# pc_healthypi_5_7.net
KiCad netlist of a schematic drawn in EAGLE
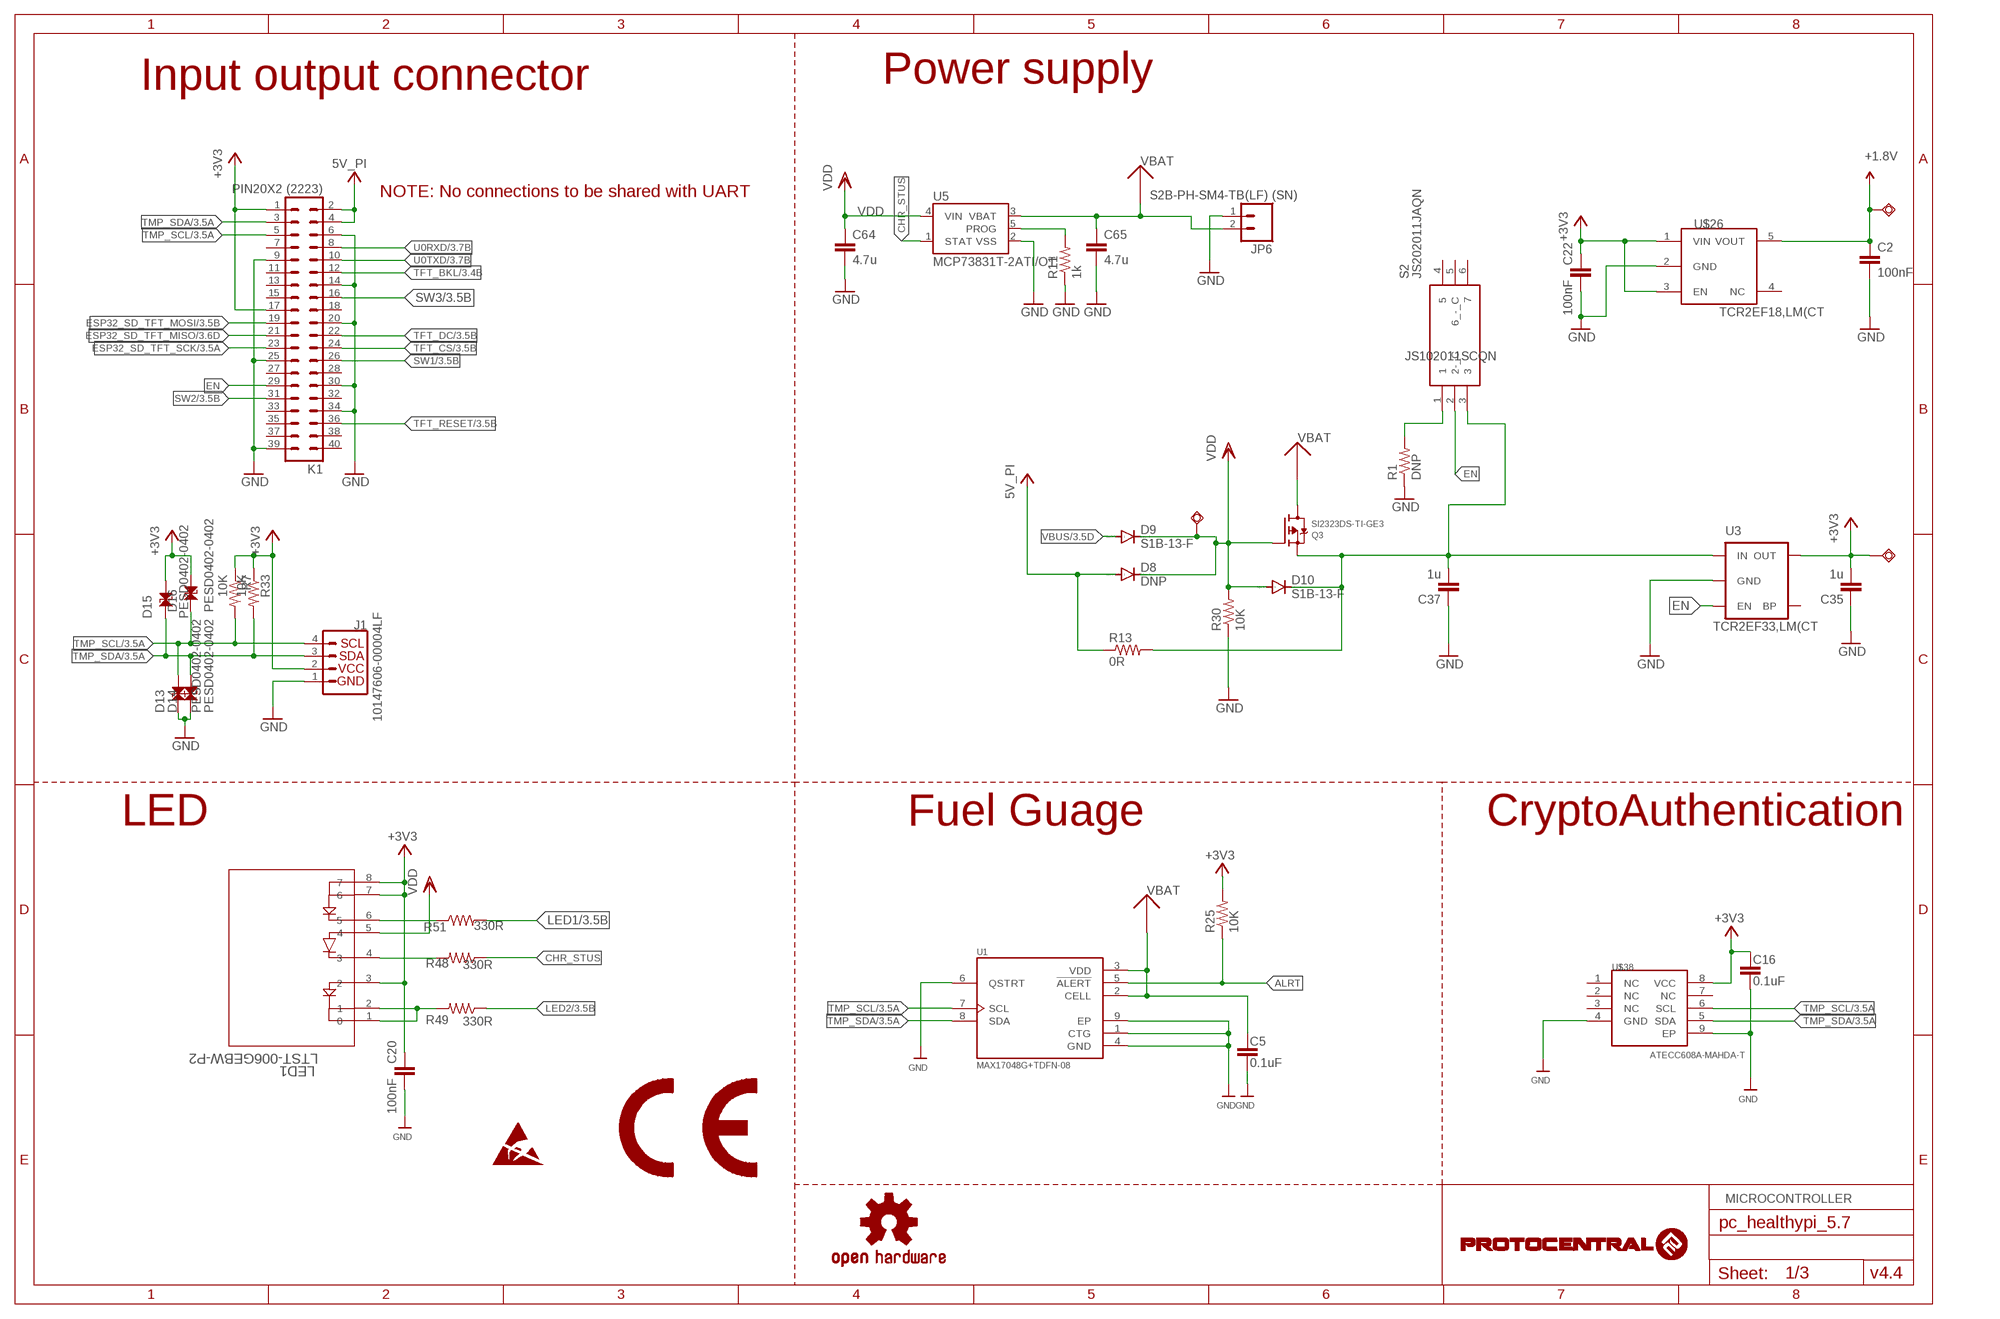
[diagram p0: schematic, sheet 1]
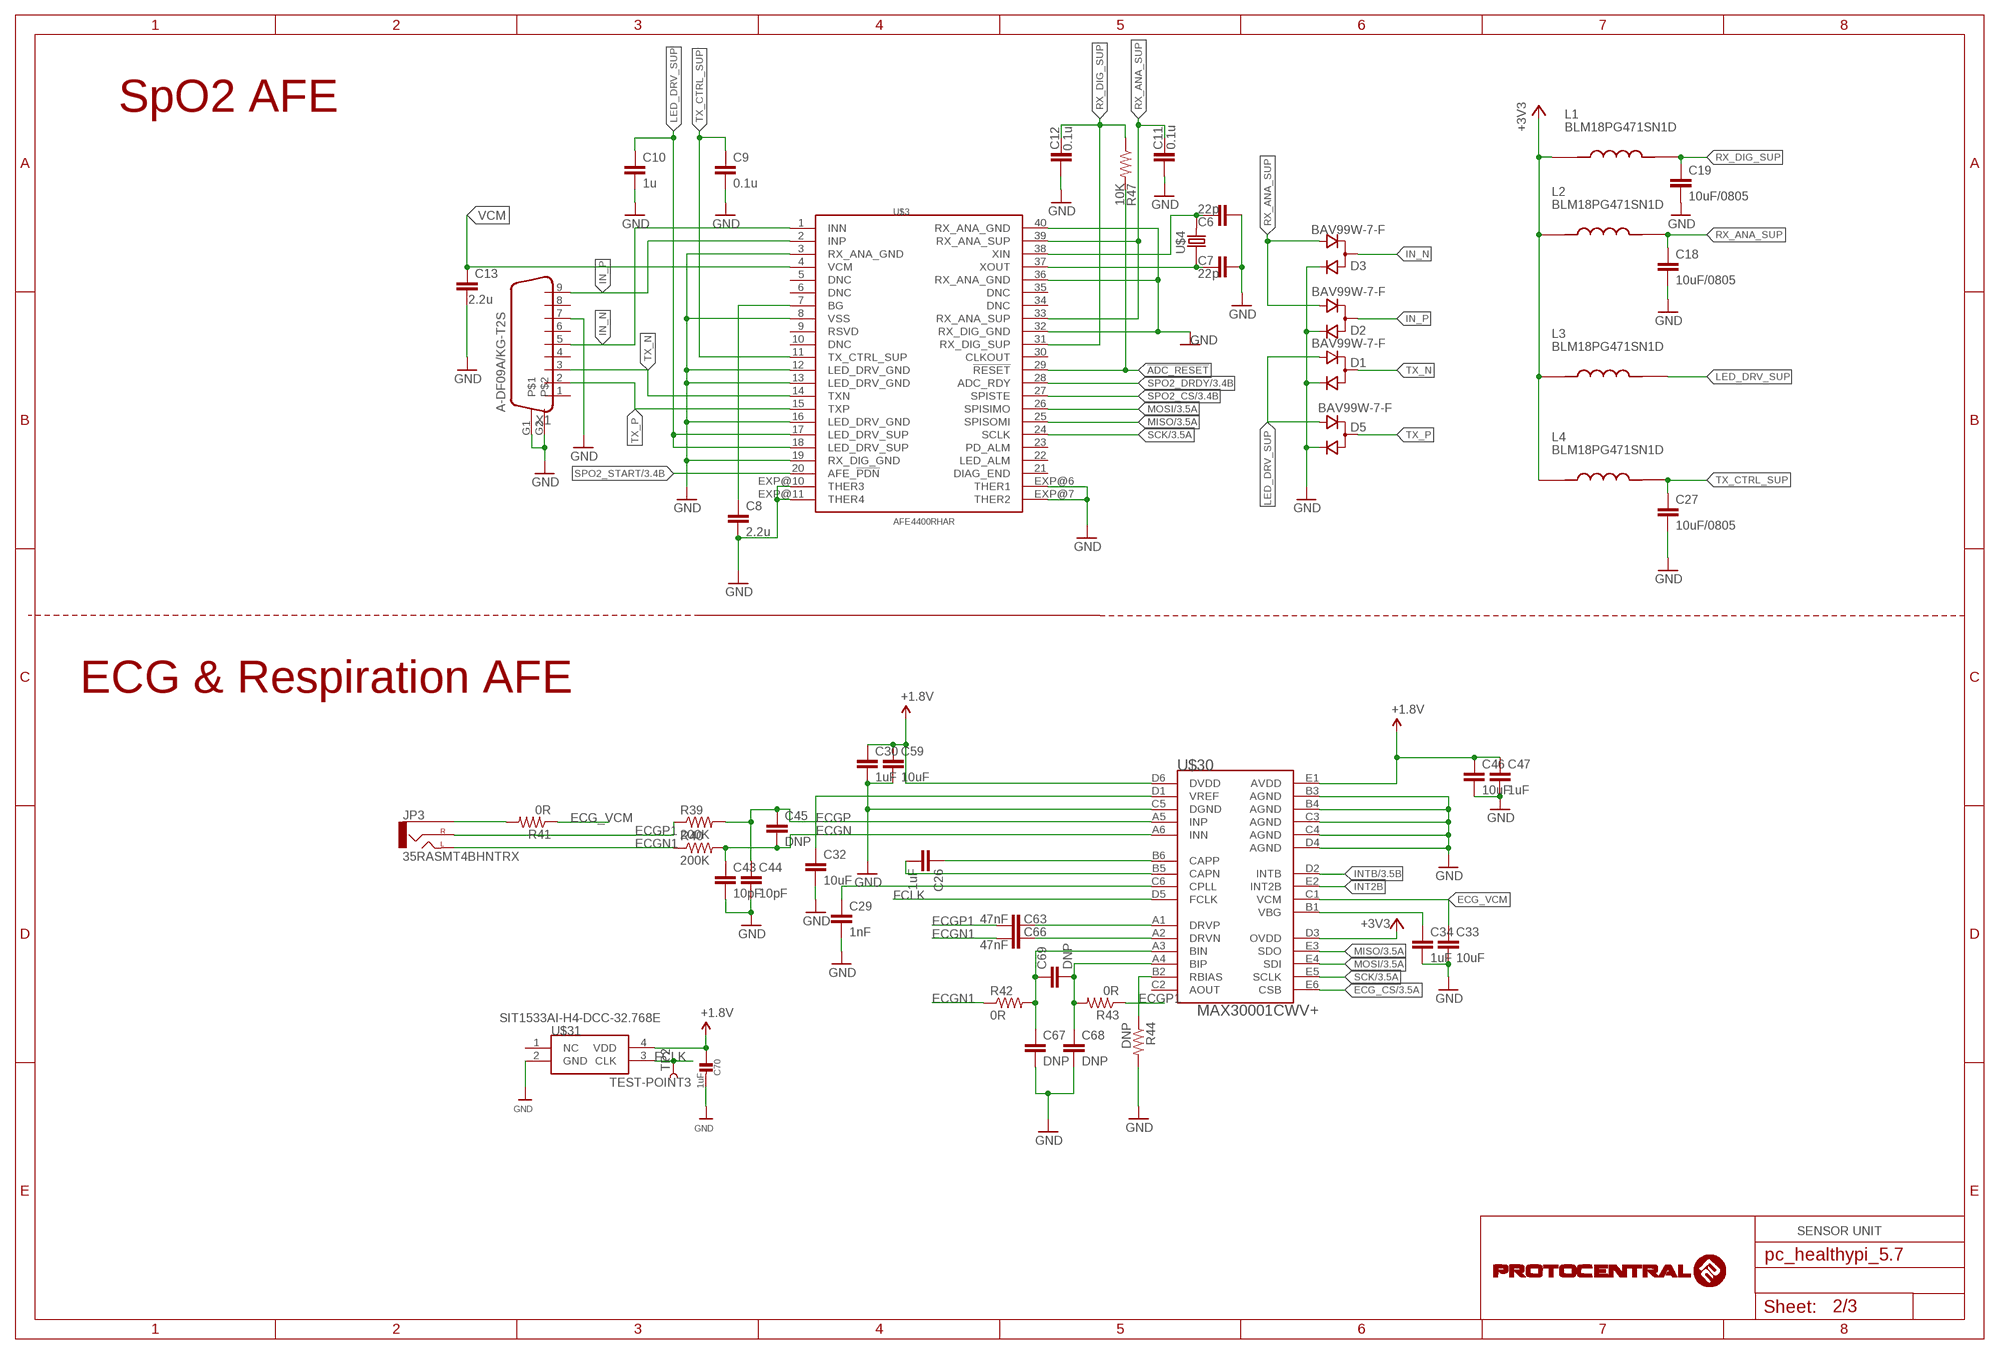
[diagram p1: schematic, sheet 2]
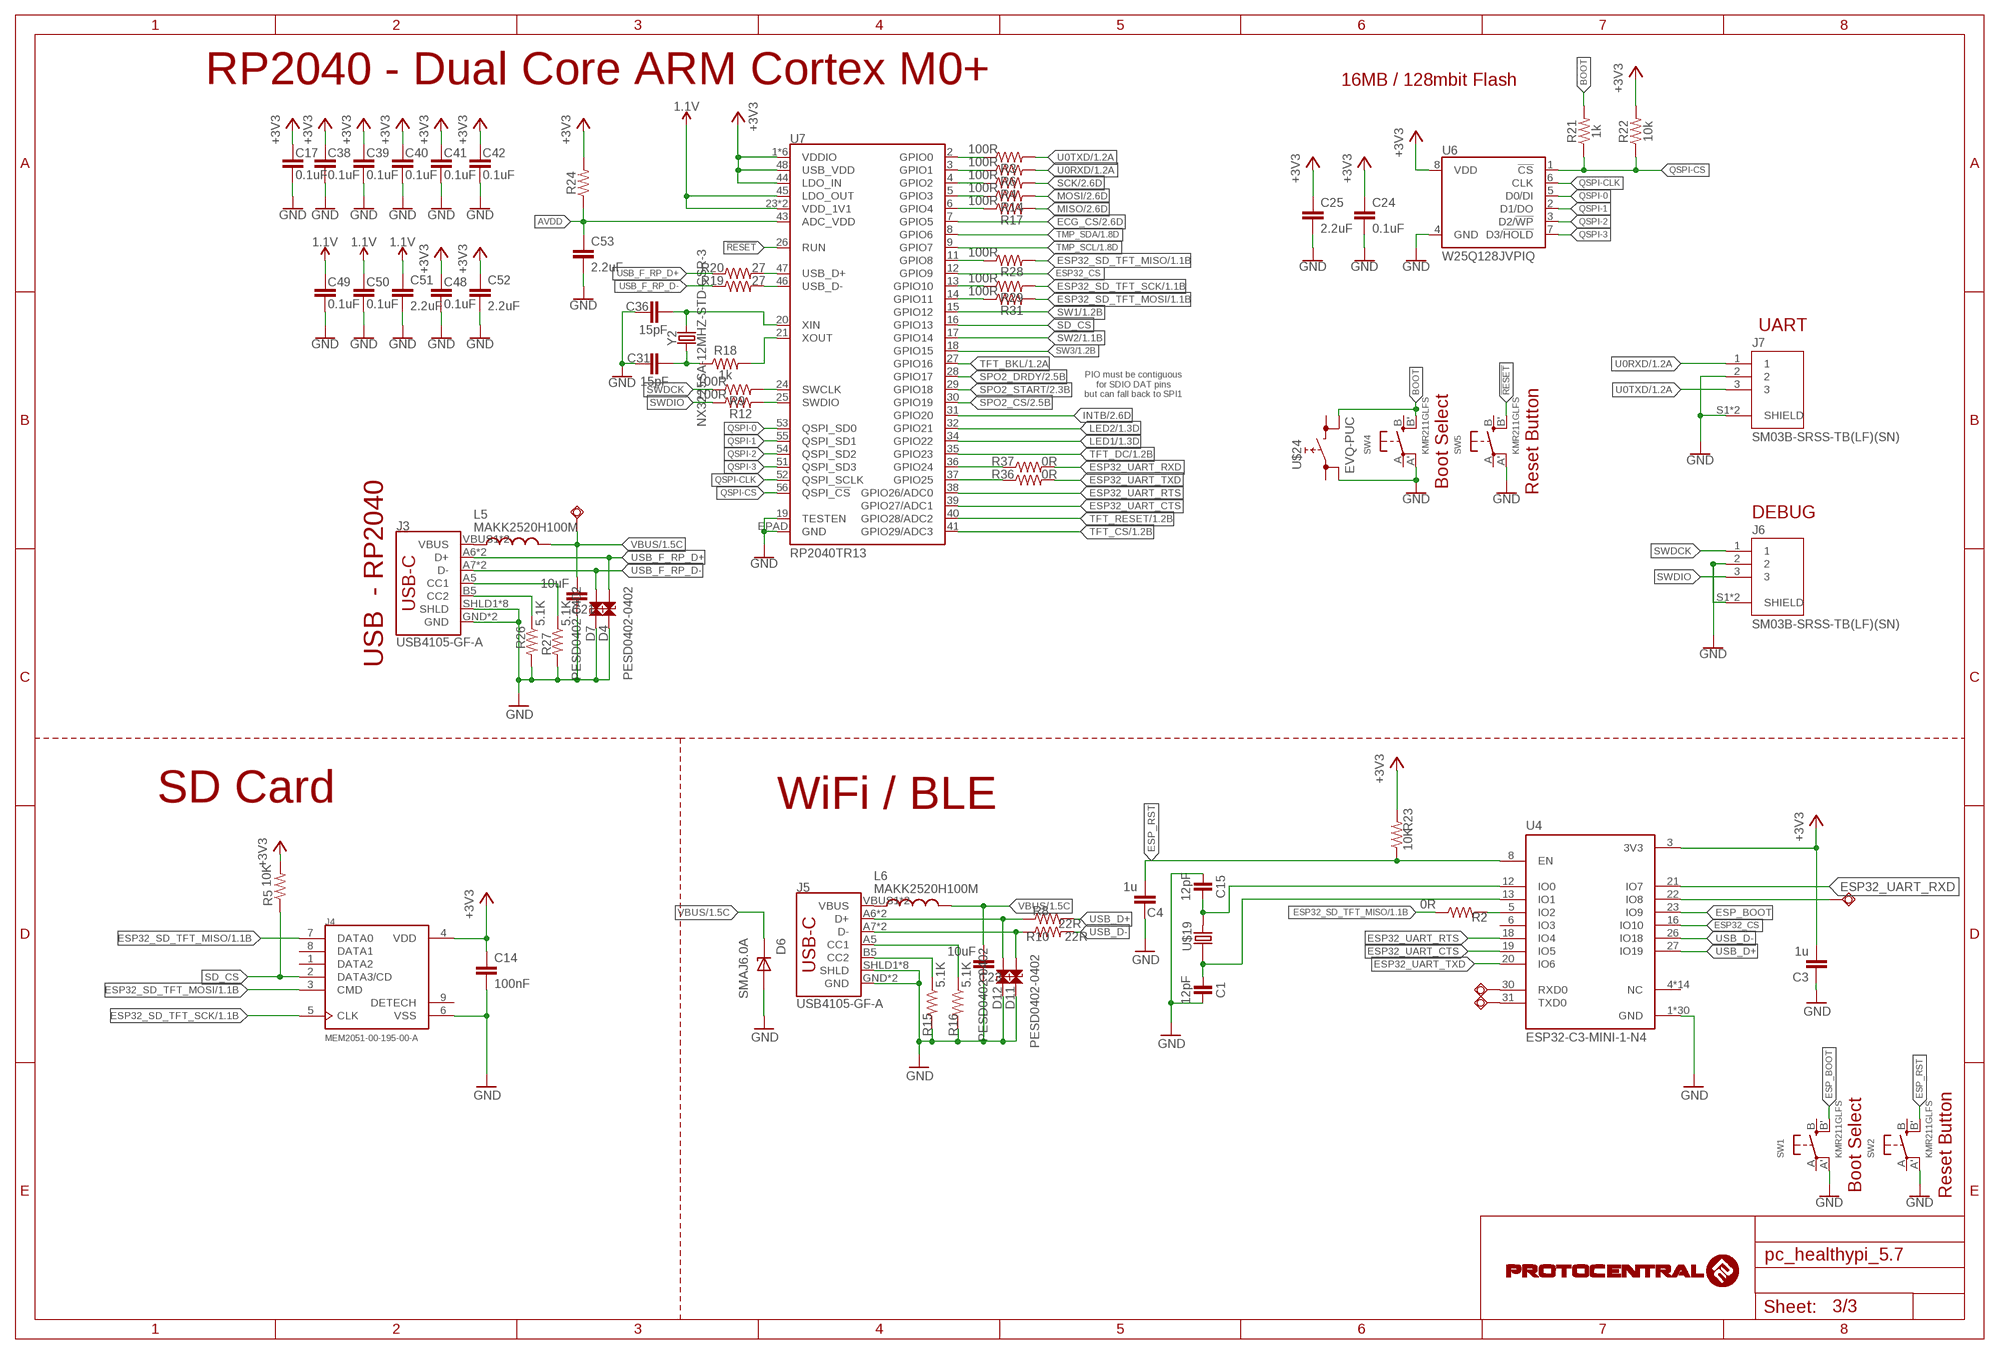
[diagram p2: schematic, sheet 3]

(export (version "E")
  (design (tool "Eeschema 10.0.6"))
  (components
    (comp (ref "C6")
      (value "22p")
      (footprint "eagle-import:C0402")
      (libsource (lib "eagle-import") (part "rcl_334_C-EUC0402"))
    )
    (comp (ref "C7")
      (value "22p")
      (footprint "eagle-import:C0402")
      (libsource (lib "eagle-import") (part "rcl_334_C-EUC0402"))
    )
    (comp (ref "C8")
      (value "2.2u")
      (footprint "eagle-import:C0402")
      (libsource (lib "eagle-import") (part "rcl_334_C-EUC0402"))
    )
    (comp (ref "C9")
      (value "0.1u")
      (footprint "eagle-import:C0402")
      (libsource (lib "eagle-import") (part "rcl_334_C-EUC0402"))
    )
    (comp (ref "C10")
      (value "1u")
      (footprint "eagle-import:C0805")
      (libsource (lib "eagle-import") (part "rcl_334_C-EUC0805"))
    )
    (comp (ref "C11")
      (value "0.1u")
      (footprint "eagle-import:C0402")
      (libsource (lib "eagle-import") (part "rcl_334_C-EUC0402"))
    )
    (comp (ref "C12")
      (value "0.1u")
      (footprint "eagle-import:C0402")
      (libsource (lib "eagle-import") (part "rcl_334_C-EUC0402"))
    )
    (comp (ref "C13")
      (value "2.2u")
      (footprint "eagle-import:C0402")
      (libsource (lib "eagle-import") (part "rcl_334_C-EUC0402"))
    )
    (comp (ref "C18")
      (value "10uF/0805")
      (footprint "eagle-import:C0805")
      (libsource (lib "eagle-import") (part "rcl_334_C-EUC0805"))
    )
    (comp (ref "C19")
      (value "10uF/0805")
      (footprint "eagle-import:C0805")
      (libsource (lib "eagle-import") (part "rcl_334_C-EUC0805"))
    )
    (comp (ref "C26")
      (value "1uF")
      (footprint "eagle-import:C0805")
      (libsource (lib "eagle-import") (part "rcl_334_C-EUC0805"))
    )
    (comp (ref "C27")
      (value "10uF/0805")
      (footprint "eagle-import:C0805")
      (libsource (lib "eagle-import") (part "rcl_334_C-EUC0805"))
    )
    (comp (ref "C29")
      (value "1nF")
      (footprint "eagle-import:C0402")
      (libsource (lib "eagle-import") (part "rcl_334_C-EUC0402"))
    )
    (comp (ref "C30")
      (value "1uF")
      (footprint "eagle-import:C0402")
      (libsource (lib "eagle-import") (part "rcl_334_C-EUC0402"))
    )
    (comp (ref "C32")
      (value "10uF")
      (footprint "eagle-import:C0805")
      (libsource (lib "eagle-import") (part "rcl_334_C-EUC0805"))
    )
    (comp (ref "C33")
      (value "10uF")
      (footprint "eagle-import:C0805")
      (libsource (lib "eagle-import") (part "rcl_334_C-EUC0805"))
    )
    (comp (ref "C34")
      (value "1uF")
      (footprint "eagle-import:C0402")
      (libsource (lib "eagle-import") (part "rcl_334_C-EUC0402"))
    )
    (comp (ref "C43")
      (value "10pF")
      (footprint "eagle-import:C0402")
      (libsource (lib "eagle-import") (part "rcl_334_C-EUC0402"))
    )
    (comp (ref "C44")
      (value "10pF")
      (footprint "eagle-import:C0402")
      (libsource (lib "eagle-import") (part "rcl_334_C-EUC0402"))
    )
    (comp (ref "C45")
      (value "DNP")
      (footprint "eagle-import:C0402")
      (libsource (lib "eagle-import") (part "rcl_334_C-EUC0402"))
    )
    (comp (ref "C46")
      (value "10uF")
      (footprint "eagle-import:C0805")
      (libsource (lib "eagle-import") (part "rcl_334_C-EUC0805"))
    )
    (comp (ref "C47")
      (value "1uF")
      (footprint "eagle-import:C0402")
      (libsource (lib "eagle-import") (part "rcl_334_C-EUC0402"))
    )
    (comp (ref "C59")
      (value "10uF")
      (footprint "eagle-import:C0805")
      (libsource (lib "eagle-import") (part "rcl_334_C-EUC0805"))
    )
    (comp (ref "C63")
      (value "47nF")
      (footprint "eagle-import:C0402")
      (libsource (lib "eagle-import") (part "rcl_334_C-EUC0402"))
    )
    (comp (ref "C66")
      (value "47nF")
      (footprint "eagle-import:C0402")
      (libsource (lib "eagle-import") (part "rcl_334_C-EUC0402"))
    )
    (comp (ref "C67")
      (value "DNP")
      (footprint "eagle-import:C0402")
      (libsource (lib "eagle-import") (part "rcl_334_C-EUC0402"))
    )
    (comp (ref "C68")
      (value "DNP")
      (footprint "eagle-import:C0402")
      (libsource (lib "eagle-import") (part "rcl_334_C-EUC0402"))
    )
    (comp (ref "C69")
      (value "DNP")
      (footprint "eagle-import:C0402")
      (libsource (lib "eagle-import") (part "rcl_334_C-EUC0402"))
    )
    (comp (ref "C70")
      (value "1uF")
      (footprint "eagle-import:0402")
      (libsource (lib "eagle-import") (part "CAP_CERAMIC0402"))
    )
    (comp (ref "D1")
      (value "BAV99W-7-F")
      (footprint "eagle-import:SOT323")
      (libsource (lib "eagle-import") (part "D_ACACSOT323"))
    )
    (comp (ref "D2")
      (value "BAV99W-7-F")
      (footprint "eagle-import:SOT323")
      (libsource (lib "eagle-import") (part "D_ACACSOT323"))
    )
    (comp (ref "D3")
      (value "BAV99W-7-F")
      (footprint "eagle-import:SOT323")
      (libsource (lib "eagle-import") (part "D_ACACSOT323"))
    )
    (comp (ref "D5")
      (value "BAV99W-7-F")
      (footprint "eagle-import:SOT323")
      (libsource (lib "eagle-import") (part "D_ACACSOT323"))
    )
    (comp (ref "JP3")
      (value "35RASMT4BHNTRX")
      (footprint "eagle-import:AUDIO-JACK-3.5MM-SMD")
      (libsource (lib "eagle-import") (part "AUDIO-JACKSMD2"))
    )
    (comp (ref "L1")
      (value "BLM18PG471SN1D")
      (footprint "eagle-import:INDC2012X105N")
      (fields (field (name "MF") "TDK") (field (name "MP") "MLZ2012N2R2LT000"))
      (libsource (lib "eagle-import") (part "MLZ2012N2R2LT000"))
    )
    (comp (ref "L2")
      (value "BLM18PG471SN1D")
      (footprint "eagle-import:INDC2012X105N")
      (fields (field (name "MF") "TDK") (field (name "MP") "MLZ2012N2R2LT000"))
      (libsource (lib "eagle-import") (part "MLZ2012N2R2LT000"))
    )
    (comp (ref "L3")
      (value "BLM18PG471SN1D")
      (footprint "eagle-import:INDC2012X105N")
      (fields (field (name "MF") "TDK") (field (name "MP") "MLZ2012N2R2LT000"))
      (libsource (lib "eagle-import") (part "MLZ2012N2R2LT000"))
    )
    (comp (ref "L4")
      (value "BLM18PG471SN1D")
      (footprint "eagle-import:INDC2012X105N")
      (fields (field (name "MF") "TDK") (field (name "MP") "MLZ2012N2R2LT000"))
      (libsource (lib "eagle-import") (part "MLZ2012N2R2LT000"))
    )
    (comp (ref "R39")
      (value "200K")
      (footprint "eagle-import:0805")
      (libsource (lib "eagle-import") (part "RESISTOR0805-RES"))
    )
    (comp (ref "R40")
      (value "200K")
      (footprint "eagle-import:0805")
      (libsource (lib "eagle-import") (part "RESISTOR0805-RES"))
    )
    (comp (ref "R41")
      (value "0R")
      (footprint "eagle-import:0805")
      (libsource (lib "eagle-import") (part "RESISTOR0805-RES"))
    )
    (comp (ref "R42")
      (value "0R")
      (footprint "eagle-import:0402-RES")
      (libsource (lib "eagle-import") (part "RESISTOR0402-RES"))
    )
    (comp (ref "R43")
      (value "0R")
      (footprint "eagle-import:0402-RES")
      (libsource (lib "eagle-import") (part "RESISTOR0402-RES"))
    )
    (comp (ref "R44")
      (value "DNP")
      (footprint "eagle-import:0402-RES")
      (libsource (lib "eagle-import") (part "RESISTOR0402-RES"))
    )
    (comp (ref "R47")
      (value "10K")
      (footprint "eagle-import:R0402")
      (libsource (lib "eagle-import") (part "rcl_334_R-US_R0402"))
    )
    (comp (ref "TP2")
      (value "TEST-POINT3")
      (footprint "eagle-import:PAD.03X.03")
      (libsource (lib "eagle-import") (part "TEST-POINT3"))
    )
    (comp (ref "U$3")
      (value "AFE4400RHAR")
      (footprint "eagle-import:QFN-40")
      (libsource (lib "eagle-import") (part "AFE4400"))
    )
    (comp (ref "U$4")
      (value "ABM3")
      (footprint "eagle-import:ABM3")
      (libsource (lib "eagle-import") (part "ABM3"))
    )
    (comp (ref "U$30")
      (value "MAX30001CWV+")
      (footprint "eagle-import:30WLP")
      (libsource (lib "eagle-import") (part "MAX30001CWV+"))
    )
    (comp (ref "U$31")
      (value "SIT1533AI-H4-DCC-32.768E")
      (footprint "eagle-import:SIT1533")
      (libsource (lib "eagle-import") (part "SIT1533"))
    )
    (comp (ref "X1")
      (value "A-DF09A/KG-T2S")
      (footprint "eagle-import:DB9")
      (libsource (lib "eagle-import") (part "DB9"))
    )
    (comp (ref "C2")
      (value "100nF")
      (footprint "eagle-import:C0402")
      (libsource (lib "eagle-import") (part "rcl_334_C-EUC0402"))
    )
    (comp (ref "C5")
      (value "0.1uF")
      (footprint "eagle-import:0402-TIGHT")
      (libsource (lib "eagle-import") (part "0.1UF-0402T-6.3V-10%-X7R"))
    )
    (comp (ref "C16")
      (value "0.1uF")
      (footprint "eagle-import:0402-TIGHT")
      (libsource (lib "eagle-import") (part "0.1UF-0402T-6.3V-10%-X7R"))
    )
    (comp (ref "C20")
      (value "100nF")
      (footprint "eagle-import:C0402")
      (libsource (lib "eagle-import") (part "rcl_334_C-EUC0402"))
    )
    (comp (ref "C22")
      (value "100nF")
      (footprint "eagle-import:C0402")
      (libsource (lib "eagle-import") (part "rcl_334_C-EUC0402"))
    )
    (comp (ref "C35")
      (value "1u")
      (footprint "eagle-import:C0402")
      (libsource (lib "eagle-import") (part "rcl_334_C-EUC0402"))
    )
    (comp (ref "C37")
      (value "1u")
      (footprint "eagle-import:C0402")
      (libsource (lib "eagle-import") (part "rcl_334_C-EUC0402"))
    )
    (comp (ref "C64")
      (value "4.7u")
      (footprint "eagle-import:C0805")
      (libsource (lib "eagle-import") (part "rcl_334_C-EUC0805"))
    )
    (comp (ref "C65")
      (value "4.7u")
      (footprint "eagle-import:C0805")
      (libsource (lib "eagle-import") (part "rcl_334_C-EUC0805"))
    )
    (comp (ref "D8")
      (value "DNP")
      (footprint "eagle-import:SOD-123_MINI-SMA")
      (libsource (lib "eagle-import") (part "CGRM400-G1"))
    )
    (comp (ref "D9")
      (value "S1B-13-F")
      (footprint "eagle-import:SOD-123_MINI-SMA")
      (libsource (lib "eagle-import") (part "CGRM400-G1"))
    )
    (comp (ref "D10")
      (value "S1B-13-F")
      (footprint "eagle-import:SOD-123_MINI-SMA")
      (libsource (lib "eagle-import") (part "CGRM400-G1"))
    )
    (comp (ref "D13")
      (value "PESD0402-0402")
      (footprint "eagle-import:0402")
      (fields
        (field (name "DIGIKEY_PART") "PESD0402-140CT-ND")
        (field (name "MOUSE_PART") "650-PESD0402-140")
      )
      (libsource (lib "eagle-import") (part "PESD0402-0402"))
    )
    (comp (ref "D14")
      (value "PESD0402-0402")
      (footprint "eagle-import:0402")
      (fields
        (field (name "DIGIKEY_PART") "PESD0402-140CT-ND")
        (field (name "MOUSE_PART") "650-PESD0402-140")
      )
      (libsource (lib "eagle-import") (part "PESD0402-0402"))
    )
    (comp (ref "D15")
      (value "PESD0402-0402")
      (footprint "eagle-import:0402")
      (fields
        (field (name "DIGIKEY_PART") "PESD0402-140CT-ND")
        (field (name "MOUSE_PART") "650-PESD0402-140")
      )
      (libsource (lib "eagle-import") (part "PESD0402-0402"))
    )
    (comp (ref "D16")
      (value "PESD0402-0402")
      (footprint "eagle-import:0402")
      (fields
        (field (name "DIGIKEY_PART") "PESD0402-140CT-ND")
        (field (name "MOUSE_PART") "650-PESD0402-140")
      )
      (libsource (lib "eagle-import") (part "PESD0402-0402"))
    )
    (comp (ref "J1")
      (value "10147606-00004LF")
      (footprint "eagle-import:JST04_1MM_RA")
      (libsource (lib "eagle-import") (part "QWIIC_CONNECTORJS-1MM"))
    )
    (comp (ref "JP6")
      (value "S2B-PH-SM4-TB(LF) (SN)")
      (footprint "eagle-import:JST-2-SMD")
      (libsource (lib "eagle-import") (part "M02-JST-2MM-SMT"))
    )
    (comp (ref "K1")
      (value "PIN20X2 (2223)")
      (footprint "eagle-import:PIN_20X2")
      (libsource (lib "eagle-import") (part "PIN20X2"))
    )
    (comp (ref "LED1")
      (value "LTST-006GEBW-P2")
      (footprint "eagle-import:LTST-008BGEW_LTO")
      (fields (field (name "COPYRIGHT") "Copyright (C) 2023 Ultra Librarian. All rights reserved."))
      (libsource (lib "eagle-import") (part "LTST-006GEBW-P2"))
    )
    (comp (ref "Q3")
      (value "SI2323DS-TI-GE3")
      (footprint "eagle-import:SOT23-R")
      (libsource (lib "eagle-import") (part "MOSFET-P"))
    )
    (comp (ref "R1")
      (value "DNP")
      (footprint "eagle-import:R0402")
      (libsource (lib "eagle-import") (part "rcl_334_R-US_R0402"))
    )
    (comp (ref "R7")
      (value "10K")
      (footprint "eagle-import:R0402")
      (libsource (lib "eagle-import") (part "rcl_334_R-US_R0402"))
    )
    (comp (ref "R11")
      (value "1k")
      (footprint "eagle-import:R0402")
      (libsource (lib "eagle-import") (part "rcl_334_R-US_R0402"))
    )
    (comp (ref "R13")
      (value "0R")
      (footprint "eagle-import:0805")
      (libsource (lib "eagle-import") (part "RESISTOR0805-RES"))
    )
    (comp (ref "R25")
      (value "10K")
      (footprint "eagle-import:0402-RES")
      (libsource (lib "eagle-import") (part "RESISTOR0402-RES"))
    )
    (comp (ref "R30")
      (value "10K")
      (footprint "eagle-import:R0402")
      (libsource (lib "eagle-import") (part "rcl_334_R-US_R0402"))
    )
    (comp (ref "R33")
      (value "10K")
      (footprint "eagle-import:R0402")
      (libsource (lib "eagle-import") (part "rcl_334_R-US_R0402"))
    )
    (comp (ref "R48")
      (value "330R")
      (footprint "eagle-import:0402-RES")
      (libsource (lib "eagle-import") (part "RESISTOR0402-RES"))
    )
    (comp (ref "R49")
      (value "330R")
      (footprint "eagle-import:0402-RES")
      (libsource (lib "eagle-import") (part "RESISTOR0402-RES"))
    )
    (comp (ref "R51")
      (value "330R")
      (footprint "eagle-import:0402-RES")
      (libsource (lib "eagle-import") (part "RESISTOR0402-RES"))
    )
    (comp (ref "S2")
      (value "JS202011JAQN")
      (footprint "eagle-import:JS202011JAQN")
      (fields (field (name "MF") "C&K"))
      (libsource (lib "eagle-import") (part "JS202011JAQN"))
    )
    (comp (ref "SWIO1")
      (value "TPSQTP11R")
      (footprint "eagle-import:TP11R")
      (libsource (lib "eagle-import") (part "TPSQTP11R"))
    )
    (comp (ref "SWIO5")
      (value "TPSQTP11R")
      (footprint "eagle-import:TP11R")
      (libsource (lib "eagle-import") (part "TPSQTP11R"))
    )
    (comp (ref "SWIO7")
      (value "TPSQTP11R")
      (footprint "eagle-import:TP11R")
      (libsource (lib "eagle-import") (part "TPSQTP11R"))
    )
    (comp (ref "U$5")
      (value "OSHW-LOGOM")
      (footprint "eagle-import:OSHW-LOGO-M")
      (libsource (lib "eagle-import") (part "OSHW-LOGOM"))
    )
    (comp (ref "U$26")
      (value "TCR2EF18,LM(CT")
      (footprint "eagle-import:SOT95P285X140-5N")
      (libsource (lib "eagle-import") (part "AP7354D-18W5-7"))
    )
    (comp (ref "U$38")
      (value "ATECC608A-MAHDA-T")
      (footprint "eagle-import:PSON50P200X300X60-9N")
      (libsource (lib "eagle-import") (part "ATECC608B-TFLXTLS"))
    )
    (comp (ref "U1")
      (value "MAX17048G+TDFN-08")
      (footprint "eagle-import:SON50P200X200X80-9N")
      (fields (field (name "MF") "Analog Devices") (field (name "MP") "MAX17048G+"))
      (libsource (lib "eagle-import") (part "MAX17048G+TDFN-08"))
    )
    (comp (ref "U3")
      (value "TCR2EF33,LM(CT")
      (footprint "eagle-import:SOT23-5")
      (libsource (lib "eagle-import") (part "V_REG_LDOSMD"))
    )
    (comp (ref "U5")
      (value "MCP73831T-2ATI/OT")
      (footprint "eagle-import:SOT23-5")
      (libsource (lib "eagle-import") (part "MCP73831"))
    )
    (comp (ref "C1")
      (value "12pF")
      (footprint "eagle-import:C0402")
      (libsource (lib "eagle-import") (part "CAPACITORS-0402"))
    )
    (comp (ref "C3")
      (value "1u")
      (footprint "eagle-import:C0402")
      (libsource (lib "eagle-import") (part "rcl_334_C-EUC0402"))
    )
    (comp (ref "C4")
      (value "1u")
      (footprint "eagle-import:C0402")
      (libsource (lib "eagle-import") (part "rcl_334_C-EUC0402"))
    )
    (comp (ref "C14")
      (value "100nF")
      (footprint "eagle-import:C0402")
      (libsource (lib "eagle-import") (part "C-EUC0402"))
    )
    (comp (ref "C15")
      (value "12pF")
      (footprint "eagle-import:C0402")
      (libsource (lib "eagle-import") (part "CAPACITORS-0402"))
    )
    (comp (ref "C17")
      (value "0.1uF")
      (footprint "eagle-import:0402-TIGHT")
      (libsource (lib "eagle-import") (part "0.1UF-0402T-6.3V-10%-X7R"))
    )
    (comp (ref "C21")
      (value "10uF")
      (footprint "eagle-import:C0805")
      (libsource (lib "eagle-import") (part "rcl_334_C-EUC0805"))
    )
    (comp (ref "C23")
      (value "10uF")
      (footprint "eagle-import:C0805")
      (libsource (lib "eagle-import") (part "rcl_334_C-EUC0805"))
    )
    (comp (ref "C24")
      (value "0.1uF")
      (footprint "eagle-import:0402-TIGHT")
      (libsource (lib "eagle-import") (part "0.1UF-0402T-6.3V-10%-X7R"))
    )
    (comp (ref "C25")
      (value "2.2uF")
      (footprint "eagle-import:0402-TIGHT")
      (libsource (lib "eagle-import") (part "2.2UF-0402_TIGHT-10V-10%-X5R"))
    )
    (comp (ref "C31")
      (value "15pF")
      (footprint "eagle-import:0402-TIGHT")
      (libsource (lib "eagle-import") (part "15PF-0402T-50V-5%"))
    )
    (comp (ref "C36")
      (value "15pF")
      (footprint "eagle-import:0402-TIGHT")
      (libsource (lib "eagle-import") (part "15PF-0402T-50V-5%"))
    )
    (comp (ref "C38")
      (value "0.1uF")
      (footprint "eagle-import:0402-TIGHT")
      (libsource (lib "eagle-import") (part "0.1UF-0402T-6.3V-10%-X7R"))
    )
    (comp (ref "C39")
      (value "0.1uF")
      (footprint "eagle-import:0402-TIGHT")
      (libsource (lib "eagle-import") (part "0.1UF-0402T-6.3V-10%-X7R"))
    )
    (comp (ref "C40")
      (value "0.1uF")
      (footprint "eagle-import:0402-TIGHT")
      (libsource (lib "eagle-import") (part "0.1UF-0402T-6.3V-10%-X7R"))
    )
    (comp (ref "C41")
      (value "0.1uF")
      (footprint "eagle-import:0402-TIGHT")
      (libsource (lib "eagle-import") (part "0.1UF-0402T-6.3V-10%-X7R"))
    )
    (comp (ref "C42")
      (value "0.1uF")
      (footprint "eagle-import:0402-TIGHT")
      (libsource (lib "eagle-import") (part "0.1UF-0402T-6.3V-10%-X7R"))
    )
    (comp (ref "C48")
      (value "0.1uF")
      (footprint "eagle-import:0402-TIGHT")
      (libsource (lib "eagle-import") (part "0.1UF-0402T-6.3V-10%-X7R"))
    )
    (comp (ref "C49")
      (value "0.1uF")
      (footprint "eagle-import:0402-TIGHT")
      (libsource (lib "eagle-import") (part "0.1UF-0402T-6.3V-10%-X7R"))
    )
    (comp (ref "C50")
      (value "0.1uF")
      (footprint "eagle-import:0402-TIGHT")
      (libsource (lib "eagle-import") (part "0.1UF-0402T-6.3V-10%-X7R"))
    )
    (comp (ref "C51")
      (value "2.2uF")
      (footprint "eagle-import:0402-TIGHT")
      (libsource (lib "eagle-import") (part "2.2UF-0402_TIGHT-10V-10%-X5R"))
    )
    (comp (ref "C52")
      (value "2.2uF")
      (footprint "eagle-import:0402-TIGHT")
      (libsource (lib "eagle-import") (part "2.2UF-0402_TIGHT-10V-10%-X5R"))
    )
    (comp (ref "C53")
      (value "2.2uF")
      (footprint "eagle-import:0402-TIGHT")
      (libsource (lib "eagle-import") (part "2.2UF-0402_TIGHT-10V-10%-X5R"))
    )
    (comp (ref "D4")
      (value "PESD0402-0402")
      (footprint "eagle-import:0402")
      (fields
        (field (name "DIGIKEY_PART") "PESD0402-140CT-ND")
        (field (name "MOUSE_PART") "650-PESD0402-140")
      )
      (libsource (lib "eagle-import") (part "PESD0402-0402"))
    )
    (comp (ref "D6")
      (value "SMAJ6.0A")
      (footprint "eagle-import:DIOM4325X250N")
      (fields (field (name "DIGI-KEY_PART_NUMBER") "SMAJ6.0ALFTR-ND") (field (name "MF") "Littelfuse"))
      (libsource (lib "eagle-import") (part "SMAJ6.0A"))
    )
    (comp (ref "D7")
      (value "PESD0402-0402")
      (footprint "eagle-import:0402")
      (fields
        (field (name "DIGIKEY_PART") "PESD0402-140CT-ND")
        (field (name "MOUSE_PART") "650-PESD0402-140")
      )
      (libsource (lib "eagle-import") (part "PESD0402-0402"))
    )
    (comp (ref "D11")
      (value "PESD0402-0402")
      (footprint "eagle-import:0402")
      (fields
        (field (name "DIGIKEY_PART") "PESD0402-140CT-ND")
        (field (name "MOUSE_PART") "650-PESD0402-140")
      )
      (libsource (lib "eagle-import") (part "PESD0402-0402"))
    )
    (comp (ref "D12")
      (value "PESD0402-0402")
      (footprint "eagle-import:0402")
      (fields
        (field (name "DIGIKEY_PART") "PESD0402-140CT-ND")
        (field (name "MOUSE_PART") "650-PESD0402-140")
      )
      (libsource (lib "eagle-import") (part "PESD0402-0402"))
    )
    (comp (ref "J3")
      (value "USB4105-GF-A")
      (footprint "eagle-import:USB-C-16P")
      (libsource (lib "eagle-import") (part "USB_C16PIN"))
    )
    (comp (ref "J4")
      (value "MEM2051-00-195-00-A")
      (footprint "eagle-import:GCT_MEM2051-00-195-00-A")
      (fields (field (name "MF") "Global Connector Technology"))
      (libsource (lib "eagle-import") (part "MEM2051-00-195-00-A"))
    )
    (comp (ref "J5")
      (value "USB4105-GF-A")
      (footprint "eagle-import:USB-C-16P")
      (libsource (lib "eagle-import") (part "circuitects_38825256_USB_C16PIN"))
    )
    (comp (ref "J6")
      (value "SM03B-SRSS-TB(LF)(SN)")
      (footprint "eagle-import:JST_SM03B-SRSS-TB(LF)(SN)")
      (fields (field (name "MF") "JST Sales America Inc."))
      (libsource (lib "eagle-import") (part "SM03B-SRSS-TB(LF)(SN)"))
    )
    (comp (ref "J7")
      (value "SM03B-SRSS-TB(LF)(SN)")
      (footprint "eagle-import:JST_SM03B-SRSS-TB(LF)(SN)")
      (fields (field (name "MF") "JST Sales America Inc."))
      (libsource (lib "eagle-import") (part "SM03B-SRSS-TB(LF)(SN)"))
    )
    (comp (ref "L5")
      (value "MAKK2520H100M")
      (footprint "eagle-import:INDC2520X100N")
      (fields (field (name "MF") "Taiyo Yuden"))
      (libsource (lib "eagle-import") (part "MAKK2520H100M"))
    )
    (comp (ref "L6")
      (value "MAKK2520H100M")
      (footprint "eagle-import:INDC2520X100N")
      (fields (field (name "MF") "Taiyo Yuden"))
      (libsource (lib "eagle-import") (part "MAKK2520H100M"))
    )
    (comp (ref "R2")
      (value "0R")
      (footprint "eagle-import:R0402")
      (libsource (lib "eagle-import") (part "rcl_334_R-US_R0402"))
    )
    (comp (ref "R3")
      (value "100R")
      (footprint "eagle-import:R0402")
      (libsource (lib "eagle-import") (part "rcl_334_R-US_R0402"))
    )
    (comp (ref "R4")
      (value "100R")
      (footprint "eagle-import:R0402")
      (libsource (lib "eagle-import") (part "rcl_334_R-US_R0402"))
    )
    (comp (ref "R5")
      (value "10K")
      (footprint "eagle-import:R0402")
      (libsource (lib "eagle-import") (part "R-US_R0402"))
    )
    (comp (ref "R6")
      (value "100R")
      (footprint "eagle-import:R0402")
      (libsource (lib "eagle-import") (part "rcl_334_R-US_R0402"))
    )
    (comp (ref "R8")
      (value "22R")
      (footprint "eagle-import:R0402")
      (libsource (lib "eagle-import") (part "rcl_334_R-US_R0402"))
    )
    (comp (ref "R9")
      (value "100R")
      (footprint "eagle-import:R0402")
      (libsource (lib "eagle-import") (part "rcl_334_R-US_R0402"))
    )
    (comp (ref "R10")
      (value "22R")
      (footprint "eagle-import:R0402")
      (libsource (lib "eagle-import") (part "rcl_334_R-US_R0402"))
    )
    (comp (ref "R12")
      (value "100R")
      (footprint "eagle-import:R0402")
      (libsource (lib "eagle-import") (part "rcl_334_R-US_R0402"))
    )
    (comp (ref "R14")
      (value "100R")
      (footprint "eagle-import:R0402")
      (libsource (lib "eagle-import") (part "rcl_334_R-US_R0402"))
    )
    (comp (ref "R15")
      (value "5.1K")
      (footprint "eagle-import:R0402")
      (libsource (lib "eagle-import") (part "rcl_334_R-US_R0402"))
    )
    (comp (ref "R16")
      (value "5.1K")
      (footprint "eagle-import:R0402")
      (libsource (lib "eagle-import") (part "rcl_334_R-US_R0402"))
    )
    (comp (ref "R17")
      (value "100R")
      (footprint "eagle-import:R0402")
      (libsource (lib "eagle-import") (part "rcl_334_R-US_R0402"))
    )
    (comp (ref "R18")
      (value "1k")
      (footprint "eagle-import:0402-TIGHT")
      (libsource (lib "eagle-import") (part "1KOHM-0402T-1/16W-1%"))
    )
    (comp (ref "R19")
      (value "27")
      (footprint "eagle-import:0402-TIGHT")
      (libsource (lib "eagle-import") (part "27OHM"))
    )
    (comp (ref "R20")
      (value "27")
      (footprint "eagle-import:0402-TIGHT")
      (libsource (lib "eagle-import") (part "27OHM"))
    )
    (comp (ref "R21")
      (value "1k")
      (footprint "eagle-import:0402-TIGHT")
      (libsource (lib "eagle-import") (part "1KOHM-0402T-1/16W-1%"))
    )
    (comp (ref "R22")
      (value "10k")
      (footprint "eagle-import:0402-TIGHT")
      (libsource (lib "eagle-import") (part "10KOHM-0402T-1/16W-1%"))
    )
    (comp (ref "R23")
      (value "10K")
      (footprint "eagle-import:R0402")
      (libsource (lib "eagle-import") (part "rcl_334_R-US_R0402"))
    )
    (comp (ref "R24")
      (value "200OHM-0402T-1/16W-1%")
      (footprint "eagle-import:0402-TIGHT")
      (libsource (lib "eagle-import") (part "200OHM-0402T-1/16W-1%"))
    )
    (comp (ref "R26")
      (value "5.1K")
      (footprint "eagle-import:R0402")
      (libsource (lib "eagle-import") (part "rcl_334_R-US_R0402"))
    )
    (comp (ref "R27")
      (value "5.1K")
      (footprint "eagle-import:R0402")
      (libsource (lib "eagle-import") (part "rcl_334_R-US_R0402"))
    )
    (comp (ref "R28")
      (value "100R")
      (footprint "eagle-import:R0402")
      (libsource (lib "eagle-import") (part "rcl_334_R-US_R0402"))
    )
    (comp (ref "R29")
      (value "100R")
      (footprint "eagle-import:R0402")
      (libsource (lib "eagle-import") (part "rcl_334_R-US_R0402"))
    )
    (comp (ref "R31")
      (value "100R")
      (footprint "eagle-import:R0402")
      (libsource (lib "eagle-import") (part "rcl_334_R-US_R0402"))
    )
    (comp (ref "R36")
      (value "0R")
      (footprint "eagle-import:0402-TIGHT")
      (libsource (lib "eagle-import") (part "27OHM"))
    )
    (comp (ref "R37")
      (value "0R")
      (footprint "eagle-import:0402-TIGHT")
      (libsource (lib "eagle-import") (part "27OHM"))
    )
    (comp (ref "SW1")
      (value "KMR211GLFS")
      (footprint "eagle-import:BTN_KMR2_4.6X2.8")
      (libsource (lib "eagle-import") (part "SWITCH_TACT_SMT4.6X2.8"))
    )
    (comp (ref "SW2")
      (value "KMR211GLFS")
      (footprint "eagle-import:BTN_KMR2_4.6X2.8")
      (libsource (lib "eagle-import") (part "SWITCH_TACT_SMT4.6X2.8"))
    )
    (comp (ref "SW4")
      (value "KMR211GLFS")
      (footprint "eagle-import:BTN_KMR2_4.6X2.8")
      (libsource (lib "eagle-import") (part "SWITCH_TACT_SMT4.6X2.8"))
    )
    (comp (ref "SW5")
      (value "KMR211GLFS")
      (footprint "eagle-import:BTN_KMR2_4.6X2.8")
      (libsource (lib "eagle-import") (part "SWITCH_TACT_SMT4.6X2.8"))
    )
    (comp (ref "SWIO2")
      (value "TPSQTP11R")
      (footprint "eagle-import:TP11R")
      (libsource (lib "eagle-import") (part "TPSQTP11R"))
    )
    (comp (ref "SWIO8")
      (value "TPSQTP11R")
      (footprint "eagle-import:TP11R")
      (libsource (lib "eagle-import") (part "TPSQTP11R"))
    )
    (comp (ref "SWIO9")
      (value "TPSQTP11R")
      (footprint "eagle-import:TP11R")
      (libsource (lib "eagle-import") (part "TPSQTP11R"))
    )
    (comp (ref "TP5")
      (value "TPSQTP11R")
      (footprint "eagle-import:TP11R")
      (libsource (lib "eagle-import") (part "TPSQTP11R"))
    )
    (comp (ref "U$19")
      (value "520-327-12.5-34B(32.768KHZ)")
      (footprint "eagle-import:ECX-31B")
      (libsource (lib "eagle-import") (part "ECS-X-34B"))
    )
    (comp (ref "U$24")
      (value "EVQ-PUC")
      (footprint "eagle-import:EVQ-PUC")
      (libsource (lib "eagle-import") (part "EVQ-PUC"))
    )
    (comp (ref "U4")
      (value "ESP32-C3-MINI-1-N4")
      (footprint "eagle-import:XCVR_ESP32-C3-MINI-1-N4")
      (fields (field (name "MF") "Espressif Systems"))
      (libsource (lib "eagle-import") (part "ESP32-C3-MINI-1-N4"))
    )
    (comp (ref "U6")
      (value "W25Q128JVPIQ")
      (footprint "eagle-import:WSON-8-6X5-SKINNY_CENTERPAD")
      (libsource (lib "eagle-import") (part "W25QXX128MBIT-6X5-SKINNY_CENTER"))
    )
    (comp (ref "U7")
      (value "RP2040TR13")
      (footprint "eagle-import:QFN-56")
      (libsource (lib "eagle-import") (part "RP2040"))
    )
    (comp (ref "Y2")
      (value "NX3225SA-12MHZ-STD-CSR-3")
      (footprint "eagle-import:CRYSTAL-SMD-2X2.5MM")
      (libsource (lib "eagle-import") (part "CRYSTAL-12MHZ"))
    )
  )
  (nets
    (net (code "1") (name "+1.8V") (class "Default")
      (node (ref "C2") (pin "1") (pinfunction "1_1") (pintype "passive"))
      (node (ref "C30") (pin "1") (pinfunction "1_1") (pintype "passive"))
      (node (ref "C46") (pin "1") (pinfunction "1_1") (pintype "passive"))
      (node (ref "C47") (pin "1") (pinfunction "1_1") (pintype "passive"))
      (node (ref "C59") (pin "1") (pinfunction "1_1") (pintype "passive"))
      (node (ref "C70") (pin "1") (pinfunction "P$1_1") (pintype "passive"))
      (node (ref "SWIO5") (pin "TP") (pinfunction "TP_TP") (pintype "input"))
      (node (ref "U$26") (pin "5") (pinfunction "VOUT_5") (pintype "bidirectional"))
      (node (ref "U$30") (pin "D6") (pinfunction "DVDD_D6") (pintype "bidirectional"))
      (node (ref "U$30") (pin "E1") (pinfunction "AVDD_E1") (pintype "bidirectional"))
      (node (ref "U$31") (pin "4") (pinfunction "VDD_4") (pintype "bidirectional"))
    )
    (net (code "2") (name "+3V3") (class "Default")
      (node (ref "C14") (pin "1") (pinfunction "1_1") (pintype "passive"))
      (node (ref "C16") (pin "1") (pinfunction "1_1") (pintype "passive"))
      (node (ref "C17") (pin "1") (pinfunction "1_1") (pintype "passive"))
      (node (ref "C20") (pin "1") (pinfunction "1_1") (pintype "passive"))
      (node (ref "C22") (pin "1") (pinfunction "1_1") (pintype "passive"))
      (node (ref "C24") (pin "1") (pinfunction "1_1") (pintype "passive"))
      (node (ref "C25") (pin "1") (pinfunction "1_1") (pintype "passive"))
      (node (ref "C3") (pin "2") (pinfunction "2_2") (pintype "passive"))
      (node (ref "C35") (pin "2") (pinfunction "2_2") (pintype "passive"))
      (node (ref "C38") (pin "1") (pinfunction "1_1") (pintype "passive"))
      (node (ref "C39") (pin "1") (pinfunction "1_1") (pintype "passive"))
      (node (ref "C40") (pin "1") (pinfunction "1_1") (pintype "passive"))
      (node (ref "C41") (pin "1") (pinfunction "1_1") (pintype "passive"))
      (node (ref "C42") (pin "1") (pinfunction "1_1") (pintype "passive"))
      (node (ref "C48") (pin "1") (pinfunction "1_1") (pintype "passive"))
      (node (ref "C52") (pin "1") (pinfunction "1_1") (pintype "passive"))
      (node (ref "D15") (pin "2") (pinfunction "2_2") (pintype "bidirectional"))
      (node (ref "D16") (pin "2") (pinfunction "2_2") (pintype "bidirectional"))
      (node (ref "J1") (pin "2") (pinfunction "2_2") (pintype "power_in"))
      (node (ref "J4") (pin "4") (pinfunction "VDD_4") (pintype "power_in"))
      (node (ref "K1") (pin "1") (pinfunction "1_1") (pintype "passive"))
      (node (ref "K1") (pin "17") (pinfunction "17_17") (pintype "passive"))
      (node (ref "L1") (pin "1") (pinfunction "1_1") (pintype "passive"))
      (node (ref "L2") (pin "1") (pinfunction "1_1") (pintype "passive"))
      (node (ref "L3") (pin "1") (pinfunction "1_1") (pintype "passive"))
      (node (ref "L4") (pin "1") (pinfunction "1_1") (pintype "passive"))
      (node (ref "LED1") (pin "3") (pinfunction "2_3") (pintype "passive"))
      (node (ref "LED1") (pin "7") (pinfunction "6_7") (pintype "passive"))
      (node (ref "LED1") (pin "8") (pinfunction "7_8") (pintype "passive"))
      (node (ref "R22") (pin "2") (pinfunction "2_2") (pintype "passive"))
      (node (ref "R23") (pin "2") (pinfunction "2_2") (pintype "passive"))
      (node (ref "R24") (pin "2") (pinfunction "2_2") (pintype "passive"))
      (node (ref "R25") (pin "2") (pinfunction "2_2") (pintype "passive"))
      (node (ref "R33") (pin "1") (pinfunction "1_1") (pintype "passive"))
      (node (ref "R5") (pin "2") (pinfunction "2_2") (pintype "passive"))
      (node (ref "R7") (pin "1") (pinfunction "1_1") (pintype "passive"))
      (node (ref "SWIO1") (pin "TP") (pinfunction "TP_TP") (pintype "input"))
      (node (ref "U$26") (pin "1") (pinfunction "VIN_1") (pintype "bidirectional"))
      (node (ref "U$26") (pin "3") (pinfunction "EN_3") (pintype "bidirectional"))
      (node (ref "U$30") (pin "D3") (pinfunction "OVDD_D3") (pintype "bidirectional"))
      (node (ref "U$38") (pin "8") (pinfunction "VCC_8") (pintype "bidirectional"))
      (node (ref "U3") (pin "5") (pinfunction "OUT_5") (pintype "passive"))
      (node (ref "U4") (pin "3") (pinfunction "3V3_3") (pintype "power_in"))
      (node (ref "U6") (pin "8") (pinfunction "VDD_8") (pintype "bidirectional"))
      (node (ref "U7") (pin "1") (pinfunction "VDDIO_1") (pintype "bidirectional"))
      (node (ref "U7") (pin "10") (pinfunction "VDDIO_10") (pintype "bidirectional"))
      (node (ref "U7") (pin "22") (pinfunction "VDDIO_22") (pintype "bidirectional"))
      (node (ref "U7") (pin "33") (pinfunction "VDDIO_33") (pintype "bidirectional"))
      (node (ref "U7") (pin "42") (pinfunction "VDDIO_42") (pintype "bidirectional"))
      (node (ref "U7") (pin "44") (pinfunction "LDO_IN_44") (pintype "bidirectional"))
      (node (ref "U7") (pin "48") (pinfunction "USB_VDD_48") (pintype "bidirectional"))
      (node (ref "U7") (pin "49") (pinfunction "VDDIO_49") (pintype "bidirectional"))
    )
    (net (code "3") (name "+5V") (class "Default")
      (node (ref "D8") (pin "A") (pinfunction "A_A") (pintype "passive"))
      (node (ref "K1") (pin "2") (pinfunction "2_2") (pintype "passive"))
      (node (ref "K1") (pin "4") (pinfunction "4_4") (pintype "passive"))
      (node (ref "R13") (pin "1") (pinfunction "1_1") (pintype "passive"))
    )
    (net (code "4") (name "1.1V") (class "Default")
      (node (ref "C49") (pin "1") (pinfunction "1_1") (pintype "passive"))
      (node (ref "C50") (pin "1") (pinfunction "1_1") (pintype "passive"))
      (node (ref "C51") (pin "1") (pinfunction "1_1") (pintype "passive"))
      (node (ref "U7") (pin "23") (pinfunction "VDD_1V1_23") (pintype "bidirectional"))
      (node (ref "U7") (pin "45") (pinfunction "LDO_OUT_45") (pintype "bidirectional"))
      (node (ref "U7") (pin "50") (pinfunction "VDD_1V1_50") (pintype "bidirectional"))
    )
    (net (code "5") (name "ALRT") (class "Default")
      (node (ref "R25") (pin "1") (pinfunction "1_1") (pintype "passive"))
      (node (ref "U1") (pin "5") (pinfunction "~{ALERT}_5") (pintype "output"))
    )
    (net (code "6") (name "AVDD") (class "Default")
      (node (ref "C53") (pin "1") (pinfunction "1_1") (pintype "passive"))
      (node (ref "R24") (pin "1") (pinfunction "1_1") (pintype "passive"))
      (node (ref "U7") (pin "43") (pinfunction "ADC_VDD_43") (pintype "bidirectional"))
    )
    (net (code "7") (name "BOOT") (class "Default")
      (node (ref "R21") (pin "2") (pinfunction "2_2") (pintype "passive"))
      (node (ref "SW4") (pin "B'") (pinfunction "S1_B'") (pintype "passive"))
      (node (ref "U$24") (pin "2") (pinfunction "1_2") (pintype "passive"))
    )
    (net (code "8") (name "CHR_STUS") (class "Default")
      (node (ref "R48") (pin "1") (pinfunction "1_1") (pintype "passive"))
      (node (ref "U5") (pin "1") (pinfunction "STAT_1") (pintype "output"))
    )
    (net (code "9") (name "ECGN") (class "Default")
      (node (ref "C43") (pin "1") (pinfunction "1_1") (pintype "passive"))
      (node (ref "C45") (pin "2") (pinfunction "2_2") (pintype "passive"))
      (node (ref "R40") (pin "2") (pinfunction "2_2") (pintype "passive"))
      (node (ref "U$30") (pin "A6") (pinfunction "INN_A6") (pintype "bidirectional"))
    )
    (net (code "10") (name "ECGN1") (class "Default")
      (node (ref "C66") (pin "1") (pinfunction "1_1") (pintype "passive"))
      (node (ref "JP3") (pin "TIP") (pinfunction "LEFT_TIP") (pintype "bidirectional"))
      (node (ref "R40") (pin "1") (pinfunction "1_1") (pintype "passive"))
      (node (ref "R42") (pin "1") (pinfunction "1_1") (pintype "passive"))
    )
    (net (code "11") (name "ECGP") (class "Default")
      (node (ref "C44") (pin "1") (pinfunction "1_1") (pintype "passive"))
      (node (ref "C45") (pin "1") (pinfunction "1_1") (pintype "passive"))
      (node (ref "R39") (pin "2") (pinfunction "2_2") (pintype "passive"))
      (node (ref "U$30") (pin "A5") (pinfunction "INP_A5") (pintype "bidirectional"))
    )
    (net (code "12") (name "ECGP1") (class "Default")
      (node (ref "C63") (pin "1") (pinfunction "1_1") (pintype "passive"))
      (node (ref "JP3") (pin "RING") (pinfunction "RIGHT_RING") (pintype "bidirectional"))
      (node (ref "R39") (pin "1") (pinfunction "1_1") (pintype "passive"))
      (node (ref "R43") (pin "1") (pinfunction "1_1") (pintype "passive"))
    )
    (net (code "13") (name "ECG_CS") (class "Default")
      (node (ref "U$30") (pin "E6") (pinfunction "CSB_E6") (pintype "bidirectional"))
      (node (ref "U7") (pin "7") (pinfunction "GPIO5_7") (pintype "bidirectional"))
    )
    (net (code "14") (name "ECG_VCM") (class "Default")
      (node (ref "C33") (pin "1") (pinfunction "1_1") (pintype "passive"))
      (node (ref "R41") (pin "1") (pinfunction "1_1") (pintype "passive"))
      (node (ref "U$30") (pin "C1") (pinfunction "VCM_C1") (pintype "bidirectional"))
    )
    (net (code "15") (name "EN") (class "Default")
      (node (ref "K1") (pin "29") (pinfunction "29_29") (pintype "passive"))
      (node (ref "S2") (pin "2") (pinfunction "2-_C_2") (pintype "bidirectional"))
      (node (ref "U3") (pin "3") (pinfunction "EN_3") (pintype "input"))
    )
    (net (code "16") (name "ESP32_CS") (class "Default")
      (node (ref "U4") (pin "16") (pinfunction "IO10_16") (pintype "bidirectional"))
      (node (ref "U7") (pin "12") (pinfunction "GPIO9_12") (pintype "bidirectional"))
    )
    (net (code "17") (name "ESP32_SD_TFT_MISO") (class "Default")
      (node (ref "J4") (pin "7") (pinfunction "DATA0_7") (pintype "bidirectional"))
      (node (ref "K1") (pin "21") (pinfunction "21_21") (pintype "passive"))
      (node (ref "R2") (pin "1") (pinfunction "1_1") (pintype "passive"))
      (node (ref "R28") (pin "2") (pinfunction "2_2") (pintype "passive"))
    )
    (net (code "18") (name "ESP32_SD_TFT_MOSI") (class "Default")
      (node (ref "J4") (pin "3") (pinfunction "CMD_3") (pintype "bidirectional"))
      (node (ref "K1") (pin "19") (pinfunction "19_19") (pintype "passive"))
      (node (ref "R31") (pin "2") (pinfunction "2_2") (pintype "passive"))
    )
    (net (code "19") (name "ESP32_SD_TFT_SCK") (class "Default")
      (node (ref "J4") (pin "5") (pinfunction "CLK_5") (pintype "bidirectional"))
      (node (ref "K1") (pin "23") (pinfunction "23_23") (pintype "passive"))
      (node (ref "R29") (pin "2") (pinfunction "2_2") (pintype "passive"))
    )
    (net (code "20") (name "ESP32_UART_CTS") (class "Default")
      (node (ref "U4") (pin "19") (pinfunction "IO5_19") (pintype "bidirectional"))
      (node (ref "U7") (pin "39") (pinfunction "GPIO27/ADC1_39") (pintype "bidirectional"))
    )
    (net (code "21") (name "ESP32_UART_RTS") (class "Default")
      (node (ref "U4") (pin "18") (pinfunction "IO4_18") (pintype "bidirectional"))
      (node (ref "U7") (pin "38") (pinfunction "GPIO26/ADC0_38") (pintype "bidirectional"))
    )
    (net (code "22") (name "ESP32_UART_RXD") (class "Default")
      (node (ref "R37") (pin "2") (pinfunction "2_2") (pintype "passive"))
      (node (ref "U4") (pin "21") (pinfunction "IO7_21") (pintype "bidirectional"))
    )
    (net (code "23") (name "ESP32_UART_TXD") (class "Default")
      (node (ref "R36") (pin "2") (pinfunction "2_2") (pintype "passive"))
      (node (ref "U4") (pin "20") (pinfunction "IO6_20") (pintype "bidirectional"))
    )
    (net (code "24") (name "ESP_BOOT") (class "Default")
      (node (ref "SW1") (pin "B'") (pinfunction "S1_B'") (pintype "passive"))
      (node (ref "U4") (pin "23") (pinfunction "IO9_23") (pintype "bidirectional"))
    )
    (net (code "25") (name "ESP_RST") (class "Default")
      (node (ref "C4") (pin "2") (pinfunction "2_2") (pintype "passive"))
      (node (ref "R23") (pin "1") (pinfunction "1_1") (pintype "passive"))
      (node (ref "SW2") (pin "B'") (pinfunction "S1_B'") (pintype "passive"))
      (node (ref "U4") (pin "8") (pinfunction "EN_8") (pintype "input"))
    )
    (net (code "26") (name "FCLK") (class "Default")
      (node (ref "TP2") (pin "P$1") (pinfunction "1_P$1") (pintype "bidirectional"))
      (node (ref "U$30") (pin "D5") (pinfunction "FCLK_D5") (pintype "bidirectional"))
      (node (ref "U$31") (pin "3") (pinfunction "CLK_3") (pintype "bidirectional"))
    )
    (net (code "27") (name "GND") (class "Default")
      (node (ref "C1") (pin "2") (pinfunction "2_2") (pintype "passive"))
      (node (ref "C10") (pin "2") (pinfunction "2_2") (pintype "passive"))
      (node (ref "C11") (pin "2") (pinfunction "2_2") (pintype "passive"))
      (node (ref "C12") (pin "2") (pinfunction "2_2") (pintype "passive"))
      (node (ref "C13") (pin "2") (pinfunction "2_2") (pintype "passive"))
      (node (ref "C14") (pin "2") (pinfunction "2_2") (pintype "passive"))
      (node (ref "C15") (pin "1") (pinfunction "1_1") (pintype "passive"))
      (node (ref "C16") (pin "2") (pinfunction "2_2") (pintype "passive"))
      (node (ref "C17") (pin "2") (pinfunction "2_2") (pintype "passive"))
      (node (ref "C18") (pin "2") (pinfunction "2_2") (pintype "passive"))
      (node (ref "C19") (pin "2") (pinfunction "2_2") (pintype "passive"))
      (node (ref "C2") (pin "2") (pinfunction "2_2") (pintype "passive"))
      (node (ref "C20") (pin "2") (pinfunction "2_2") (pintype "passive"))
      (node (ref "C21") (pin "1") (pinfunction "1_1") (pintype "passive"))
      (node (ref "C22") (pin "2") (pinfunction "2_2") (pintype "passive"))
      (node (ref "C23") (pin "1") (pinfunction "1_1") (pintype "passive"))
      (node (ref "C24") (pin "2") (pinfunction "2_2") (pintype "passive"))
      (node (ref "C25") (pin "2") (pinfunction "2_2") (pintype "passive"))
      (node (ref "C27") (pin "2") (pinfunction "2_2") (pintype "passive"))
      (node (ref "C29") (pin "2") (pinfunction "2_2") (pintype "passive"))
      (node (ref "C3") (pin "1") (pinfunction "1_1") (pintype "passive"))
      (node (ref "C30") (pin "2") (pinfunction "2_2") (pintype "passive"))
      (node (ref "C31") (pin "1") (pinfunction "1_1") (pintype "passive"))
      (node (ref "C32") (pin "2") (pinfunction "2_2") (pintype "passive"))
      (node (ref "C33") (pin "2") (pinfunction "2_2") (pintype "passive"))
      (node (ref "C34") (pin "2") (pinfunction "2_2") (pintype "passive"))
      (node (ref "C35") (pin "1") (pinfunction "1_1") (pintype "passive"))
      (node (ref "C36") (pin "1") (pinfunction "1_1") (pintype "passive"))
      (node (ref "C37") (pin "1") (pinfunction "1_1") (pintype "passive"))
      (node (ref "C38") (pin "2") (pinfunction "2_2") (pintype "passive"))
      (node (ref "C39") (pin "2") (pinfunction "2_2") (pintype "passive"))
      (node (ref "C4") (pin "1") (pinfunction "1_1") (pintype "passive"))
      (node (ref "C40") (pin "2") (pinfunction "2_2") (pintype "passive"))
      (node (ref "C41") (pin "2") (pinfunction "2_2") (pintype "passive"))
      (node (ref "C42") (pin "2") (pinfunction "2_2") (pintype "passive"))
      (node (ref "C43") (pin "2") (pinfunction "2_2") (pintype "passive"))
      (node (ref "C44") (pin "2") (pinfunction "2_2") (pintype "passive"))
      (node (ref "C46") (pin "2") (pinfunction "2_2") (pintype "passive"))
      (node (ref "C47") (pin "2") (pinfunction "2_2") (pintype "passive"))
      (node (ref "C48") (pin "2") (pinfunction "2_2") (pintype "passive"))
      (node (ref "C49") (pin "2") (pinfunction "2_2") (pintype "passive"))
      (node (ref "C5") (pin "2") (pinfunction "2_2") (pintype "passive"))
      (node (ref "C50") (pin "2") (pinfunction "2_2") (pintype "passive"))
      (node (ref "C51") (pin "2") (pinfunction "2_2") (pintype "passive"))
      (node (ref "C52") (pin "2") (pinfunction "2_2") (pintype "passive"))
      (node (ref "C53") (pin "2") (pinfunction "2_2") (pintype "passive"))
      (node (ref "C59") (pin "2") (pinfunction "2_2") (pintype "passive"))
      (node (ref "C6") (pin "1") (pinfunction "1_1") (pintype "passive"))
      (node (ref "C64") (pin "2") (pinfunction "2_2") (pintype "passive"))
      (node (ref "C65") (pin "2") (pinfunction "2_2") (pintype "passive"))
      (node (ref "C67") (pin "2") (pinfunction "2_2") (pintype "passive"))
      (node (ref "C68") (pin "2") (pinfunction "2_2") (pintype "passive"))
      (node (ref "C7") (pin "1") (pinfunction "1_1") (pintype "passive"))
      (node (ref "C70") (pin "2") (pinfunction "P$2_2") (pintype "passive"))
      (node (ref "C8") (pin "2") (pinfunction "2_2") (pintype "passive"))
      (node (ref "C9") (pin "2") (pinfunction "2_2") (pintype "passive"))
      (node (ref "D1") (pin "2") (pinfunction "C_2") (pintype "passive"))
      (node (ref "D11") (pin "1") (pinfunction "1_1") (pintype "bidirectional"))
      (node (ref "D12") (pin "1") (pinfunction "1_1") (pintype "bidirectional"))
      (node (ref "D13") (pin "1") (pinfunction "1_1") (pintype "bidirectional"))
      (node (ref "D14") (pin "1") (pinfunction "1_1") (pintype "bidirectional"))
      (node (ref "D2") (pin "2") (pinfunction "C_2") (pintype "passive"))
      (node (ref "D3") (pin "2") (pinfunction "C_2") (pintype "passive"))
      (node (ref "D4") (pin "1") (pinfunction "1_1") (pintype "bidirectional"))
      (node (ref "D5") (pin "2") (pinfunction "C_2") (pintype "passive"))
      (node (ref "D6") (pin "A") (pinfunction "A_A") (pintype "passive"))
      (node (ref "D7") (pin "1") (pinfunction "1_1") (pintype "bidirectional"))
      (node (ref "J1") (pin "1") (pinfunction "1_1") (pintype "power_in"))
      (node (ref "J3") (pin "GND") (pinfunction "GND_GND") (pintype "bidirectional"))
      (node (ref "J3") (pin "GND2") (pinfunction "GND_GND2") (pintype "bidirectional"))
      (node (ref "J3") (pin "SHLD1") (pinfunction "SHLD_SHLD1") (pintype "bidirectional"))
      (node (ref "J3") (pin "SHLD2") (pinfunction "SHLD_SHLD2") (pintype "bidirectional"))
      (node (ref "J3") (pin "SHLD3") (pinfunction "SHLD_SHLD3") (pintype "bidirectional"))
      (node (ref "J3") (pin "SHLD4") (pinfunction "SHLD_SHLD4") (pintype "bidirectional"))
      (node (ref "J3") (pin "SHLD5") (pinfunction "SHLD_SHLD5") (pintype "bidirectional"))
      (node (ref "J3") (pin "SHLD6") (pinfunction "SHLD_SHLD6") (pintype "bidirectional"))
      (node (ref "J3") (pin "SHLD7") (pinfunction "SHLD_SHLD7") (pintype "bidirectional"))
      (node (ref "J3") (pin "SHLD8") (pinfunction "SHLD_SHLD8") (pintype "bidirectional"))
      (node (ref "J4") (pin "6") (pinfunction "VSS_6") (pintype "power_in"))
      (node (ref "J5") (pin "GND") (pinfunction "GND_GND") (pintype "bidirectional"))
      (node (ref "J5") (pin "GND2") (pinfunction "GND_GND2") (pintype "bidirectional"))
      (node (ref "J5") (pin "SHLD1") (pinfunction "SHLD_SHLD1") (pintype "bidirectional"))
      (node (ref "J5") (pin "SHLD2") (pinfunction "SHLD_SHLD2") (pintype "bidirectional"))
      (node (ref "J5") (pin "SHLD3") (pinfunction "SHLD_SHLD3") (pintype "bidirectional"))
      (node (ref "J5") (pin "SHLD4") (pinfunction "SHLD_SHLD4") (pintype "bidirectional"))
      (node (ref "J5") (pin "SHLD5") (pinfunction "SHLD_SHLD5") (pintype "bidirectional"))
      (node (ref "J5") (pin "SHLD6") (pinfunction "SHLD_SHLD6") (pintype "bidirectional"))
      (node (ref "J5") (pin "SHLD7") (pinfunction "SHLD_SHLD7") (pintype "bidirectional"))
      (node (ref "J5") (pin "SHLD8") (pinfunction "SHLD_SHLD8") (pintype "bidirectional"))
      (node (ref "J6") (pin "2") (pinfunction "2_2") (pintype "passive"))
      (node (ref "J6") (pin "S1") (pinfunction "SHIELD_S1") (pintype "passive"))
      (node (ref "J6") (pin "S2") (pinfunction "SHIELD_S2") (pintype "passive"))
      (node (ref "J7") (pin "2") (pinfunction "2_2") (pintype "passive"))
      (node (ref "J7") (pin "S1") (pinfunction "SHIELD_S1") (pintype "passive"))
      (node (ref "J7") (pin "S2") (pinfunction "SHIELD_S2") (pintype "passive"))
      (node (ref "JP6") (pin "1") (pinfunction "1_1") (pintype "passive"))
      (node (ref "K1") (pin "14") (pinfunction "14_14") (pintype "passive"))
      (node (ref "K1") (pin "20") (pinfunction "20_20") (pintype "passive"))
      (node (ref "K1") (pin "25") (pinfunction "25_25") (pintype "passive"))
      (node (ref "K1") (pin "30") (pinfunction "30_30") (pintype "passive"))
      (node (ref "K1") (pin "34") (pinfunction "34_34") (pintype "passive"))
      (node (ref "K1") (pin "39") (pinfunction "39_39") (pintype "passive"))
      (node (ref "K1") (pin "6") (pinfunction "6_6") (pintype "passive"))
      (node (ref "K1") (pin "9") (pinfunction "9_9") (pintype "passive"))
      (node (ref "R1") (pin "1") (pinfunction "1_1") (pintype "passive"))
      (node (ref "R11") (pin "1") (pinfunction "1_1") (pintype "passive"))
      (node (ref "R15") (pin "2") (pinfunction "2_2") (pintype "passive"))
      (node (ref "R16") (pin "2") (pinfunction "2_2") (pintype "passive"))
      (node (ref "R26") (pin "2") (pinfunction "2_2") (pintype "passive"))
      (node (ref "R27") (pin "2") (pinfunction "2_2") (pintype "passive"))
      (node (ref "R30") (pin "1") (pinfunction "1_1") (pintype "passive"))
      (node (ref "R44") (pin "2") (pinfunction "2_2") (pintype "passive"))
      (node (ref "SW1") (pin "A'") (pinfunction "P1_A'") (pintype "passive"))
      (node (ref "SW2") (pin "A'") (pinfunction "P1_A'") (pintype "passive"))
      (node (ref "SW4") (pin "A'") (pinfunction "P1_A'") (pintype "passive"))
      (node (ref "SW5") (pin "A'") (pinfunction "P1_A'") (pintype "passive"))
      (node (ref "U$24") (pin "3") (pinfunction "0_3") (pintype "passive"))
      (node (ref "U$26") (pin "2") (pinfunction "GND_2") (pintype "bidirectional"))
      (node (ref "U$3") (pin "12") (pinfunction "LED_DRV_GND_12") (pintype "bidirectional"))
      (node (ref "U$3") (pin "13") (pinfunction "LED_DRV_GND_13") (pintype "bidirectional"))
      (node (ref "U$3") (pin "16") (pinfunction "LED_DRV_GND_16") (pintype "bidirectional"))
      (node (ref "U$3") (pin "19") (pinfunction "RX_DIG_GND_19") (pintype "bidirectional"))
      (node (ref "U$3") (pin "3") (pinfunction "RX_ANA_GND_3") (pintype "bidirectional"))
      (node (ref "U$3") (pin "32") (pinfunction "RX_DIG_GND_32") (pintype "bidirectional"))
      (node (ref "U$3") (pin "36") (pinfunction "RX_ANA_GND_36") (pintype "bidirectional"))
      (node (ref "U$3") (pin "40") (pinfunction "RX_ANA_GND_40") (pintype "bidirectional"))
      (node (ref "U$3") (pin "8") (pinfunction "VSS_8") (pintype "bidirectional"))
      (node (ref "U$3") (pin "EXP@10") (pinfunction "THER3_EXP@10") (pintype "bidirectional"))
      (node (ref "U$3") (pin "EXP@11") (pinfunction "THER4_EXP@11") (pintype "bidirectional"))
      (node (ref "U$3") (pin "EXP@6") (pinfunction "THER1_EXP@6") (pintype "bidirectional"))
      (node (ref "U$3") (pin "EXP@7") (pinfunction "THER2_EXP@7") (pintype "bidirectional"))
      (node (ref "U$30") (pin "B3") (pinfunction "AGND_B3") (pintype "bidirectional"))
      (node (ref "U$30") (pin "B4") (pinfunction "AGND_B4") (pintype "bidirectional"))
      (node (ref "U$30") (pin "C3") (pinfunction "AGND_C3") (pintype "bidirectional"))
      (node (ref "U$30") (pin "C4") (pinfunction "AGND_C4") (pintype "bidirectional"))
      (node (ref "U$30") (pin "C5") (pinfunction "DGND_C5") (pintype "bidirectional"))
      (node (ref "U$30") (pin "D4") (pinfunction "AGND_D4") (pintype "bidirectional"))
      (node (ref "U$31") (pin "2") (pinfunction "GND_2") (pintype "bidirectional"))
      (node (ref "U$38") (pin "4") (pinfunction "GND_4") (pintype "bidirectional"))
      (node (ref "U$38") (pin "9") (pinfunction "EP_9") (pintype "bidirectional"))
      (node (ref "U1") (pin "1") (pinfunction "CTG_1") (pintype "power_in"))
      (node (ref "U1") (pin "4") (pinfunction "GND_4") (pintype "power_in"))
      (node (ref "U1") (pin "6") (pinfunction "QSTRT_6") (pintype "input"))
      (node (ref "U1") (pin "9") (pinfunction "EP_9") (pintype "power_in"))
      (node (ref "U3") (pin "2") (pinfunction "GND_2") (pintype "input"))
      (node (ref "U4") (pin "1") (pinfunction "GND_1") (pintype "power_in"))
      (node (ref "U4") (pin "11") (pinfunction "GND_11") (pintype "power_in"))
      (node (ref "U4") (pin "14") (pinfunction "GND_14") (pintype "power_in"))
      (node (ref "U4") (pin "2") (pinfunction "GND_2") (pintype "power_in"))
      (node (ref "U4") (pin "36") (pinfunction "GND_36") (pintype "power_in"))
      (node (ref "U4") (pin "37") (pinfunction "GND_37") (pintype "power_in"))
      (node (ref "U4") (pin "38") (pinfunction "GND_38") (pintype "power_in"))
      (node (ref "U4") (pin "39") (pinfunction "GND_39") (pintype "power_in"))
      (node (ref "U4") (pin "40") (pinfunction "GND_40") (pintype "power_in"))
      (node (ref "U4") (pin "41") (pinfunction "GND_41") (pintype "power_in"))
      (node (ref "U4") (pin "42") (pinfunction "GND_42") (pintype "power_in"))
      (node (ref "U4") (pin "43") (pinfunction "GND_43") (pintype "power_in"))
      (node (ref "U4") (pin "44") (pinfunction "GND_44") (pintype "power_in"))
      (node (ref "U4") (pin "45") (pinfunction "GND_45") (pintype "power_in"))
      (node (ref "U4") (pin "46") (pinfunction "GND_46") (pintype "power_in"))
      (node (ref "U4") (pin "47") (pinfunction "GND_47") (pintype "power_in"))
      (node (ref "U4") (pin "48") (pinfunction "GND_48") (pintype "power_in"))
      (node (ref "U4") (pin "49_1") (pinfunction "GND_49_1") (pintype "power_in"))
      (node (ref "U4") (pin "49_2") (pinfunction "GND_49_2") (pintype "power_in"))
      (node (ref "U4") (pin "49_3") (pinfunction "GND_49_3") (pintype "power_in"))
      (node (ref "U4") (pin "49_4") (pinfunction "GND_49_4") (pintype "power_in"))
      (node (ref "U4") (pin "49_5") (pinfunction "GND_49_5") (pintype "power_in"))
      (node (ref "U4") (pin "49_6") (pinfunction "GND_49_6") (pintype "power_in"))
      (node (ref "U4") (pin "49_7") (pinfunction "GND_49_7") (pintype "power_in"))
      (node (ref "U4") (pin "49_8") (pinfunction "GND_49_8") (pintype "power_in"))
      (node (ref "U4") (pin "49_9") (pinfunction "GND_49_9") (pintype "power_in"))
      (node (ref "U4") (pin "50") (pinfunction "GND_50") (pintype "power_in"))
      (node (ref "U4") (pin "51") (pinfunction "GND_51") (pintype "power_in"))
      (node (ref "U4") (pin "52") (pinfunction "GND_52") (pintype "power_in"))
      (node (ref "U4") (pin "53") (pinfunction "GND_53") (pintype "power_in"))
      (node (ref "U5") (pin "2") (pinfunction "VSS_2") (pintype "power_in"))
      (node (ref "U6") (pin "4") (pinfunction "GND_4") (pintype "bidirectional"))
      (node (ref "U7") (pin "19") (pinfunction "TESTEN_19") (pintype "bidirectional"))
      (node (ref "U7") (pin "EPAD") (pinfunction "GND_EPAD") (pintype "bidirectional"))
      (node (ref "X1") (pin "7") (pinfunction "7_7") (pintype "passive"))
      (node (ref "X1") (pin "G1") (pinfunction "P$1_G1") (pintype "bidirectional"))
      (node (ref "X1") (pin "G2") (pinfunction "P$2_G2") (pintype "bidirectional"))
    )
    (net (code "28") (name "INT2B") (class "Default")
      (node (ref "U$30") (pin "E2") (pinfunction "INT2B_E2") (pintype "bidirectional"))
    )
    (net (code "29") (name "INTB") (class "Default")
      (node (ref "U$30") (pin "D2") (pinfunction "INTB_D2") (pintype "bidirectional"))
      (node (ref "U7") (pin "31") (pinfunction "GPIO20_31") (pintype "bidirectional"))
    )
    (net (code "30") (name "IN_N") (class "Default")
      (node (ref "D3") (pin "1") (pinfunction "CA_1") (pintype "passive"))
      (node (ref "U$3") (pin "1") (pinfunction "INN_1") (pintype "bidirectional"))
      (node (ref "X1") (pin "5") (pinfunction "5_5") (pintype "passive"))
    )
    (net (code "31") (name "IN_P") (class "Default")
      (node (ref "D2") (pin "1") (pinfunction "CA_1") (pintype "passive"))
      (node (ref "U$3") (pin "2") (pinfunction "INP_2") (pintype "bidirectional"))
      (node (ref "X1") (pin "9") (pinfunction "9_9") (pintype "passive"))
    )
    (net (code "32") (name "LED1") (class "Default")
      (node (ref "R51") (pin "2") (pinfunction "2_2") (pintype "passive"))
      (node (ref "U7") (pin "34") (pinfunction "GPIO22_34") (pintype "bidirectional"))
    )
    (net (code "33") (name "LED2") (class "Default")
      (node (ref "R49") (pin "1") (pinfunction "1_1") (pintype "passive"))
      (node (ref "U7") (pin "32") (pinfunction "GPIO21_32") (pintype "bidirectional"))
    )
    (net (code "34") (name "LED_DRV_SUP") (class "Default")
      (node (ref "C10") (pin "1") (pinfunction "1_1") (pintype "passive"))
      (node (ref "D1") (pin "3") (pinfunction "A_3") (pintype "passive"))
      (node (ref "D5") (pin "3") (pinfunction "A_3") (pintype "passive"))
      (node (ref "L3") (pin "2") (pinfunction "2_2") (pintype "passive"))
      (node (ref "U$3") (pin "17") (pinfunction "LED_DRV_SUP_17") (pintype "bidirectional"))
      (node (ref "U$3") (pin "18") (pinfunction "LED_DRV_SUP_18") (pintype "bidirectional"))
    )
    (net (code "35") (name "MISO") (class "Default")
      (node (ref "R17") (pin "2") (pinfunction "2_2") (pintype "passive"))
      (node (ref "U$3") (pin "25") (pinfunction "SPISOMI_25") (pintype "bidirectional"))
      (node (ref "U$30") (pin "E3") (pinfunction "SDO_E3") (pintype "bidirectional"))
    )
    (net (code "36") (name "MOSI") (class "Default")
      (node (ref "R14") (pin "2") (pinfunction "2_2") (pintype "passive"))
      (node (ref "U$3") (pin "26") (pinfunction "SPISIMO_26") (pintype "bidirectional"))
      (node (ref "U$30") (pin "E4") (pinfunction "SDI_E4") (pintype "bidirectional"))
    )
    (net (code "37") (name "Net-(D11-Pad2)") (class "Default")
      (node (ref "D11") (pin "2") (pinfunction "2_2") (pintype "bidirectional"))
      (node (ref "J5") (pin "A7") (pinfunction "D-_A7") (pintype "bidirectional"))
      (node (ref "J5") (pin "B7") (pinfunction "D-_B7") (pintype "bidirectional"))
      (node (ref "R10") (pin "1") (pinfunction "1_1") (pintype "passive"))
    )
    (net (code "38") (name "Net-(D12-Pad2)") (class "Default")
      (node (ref "D12") (pin "2") (pinfunction "2_2") (pintype "bidirectional"))
      (node (ref "J5") (pin "A6") (pinfunction "D+_A6") (pintype "bidirectional"))
      (node (ref "J5") (pin "B6") (pinfunction "D+_B6") (pintype "bidirectional"))
      (node (ref "R8") (pin "1") (pinfunction "1_1") (pintype "passive"))
    )
    (net (code "39") (name "Net-(J3-CC1)") (class "Default")
      (node (ref "J3") (pin "A5") (pinfunction "CC1_A5") (pintype "bidirectional"))
      (node (ref "R27") (pin "1") (pinfunction "1_1") (pintype "passive"))
    )
    (net (code "40") (name "Net-(J3-CC2)") (class "Default")
      (node (ref "J3") (pin "B5") (pinfunction "CC2_B5") (pintype "bidirectional"))
      (node (ref "R26") (pin "1") (pinfunction "1_1") (pintype "passive"))
    )
    (net (code "41") (name "Net-(J3-VBUS-PadVBUS1)") (class "Default")
      (node (ref "J3") (pin "VBUS1") (pinfunction "VBUS_VBUS1") (pintype "bidirectional"))
      (node (ref "J3") (pin "VBUS2") (pinfunction "VBUS_VBUS2") (pintype "bidirectional"))
      (node (ref "L5") (pin "1") (pinfunction "1_1") (pintype "passive"))
    )
    (net (code "42") (name "Net-(J5-CC1)") (class "Default")
      (node (ref "J5") (pin "A5") (pinfunction "CC1_A5") (pintype "bidirectional"))
      (node (ref "R16") (pin "1") (pinfunction "1_1") (pintype "passive"))
    )
    (net (code "43") (name "Net-(J5-CC2)") (class "Default")
      (node (ref "J5") (pin "B5") (pinfunction "CC2_B5") (pintype "bidirectional"))
      (node (ref "R15") (pin "1") (pinfunction "1_1") (pintype "passive"))
    )
    (net (code "44") (name "Net-(J5-VBUS-PadVBUS1)") (class "Default")
      (node (ref "J5") (pin "VBUS1") (pinfunction "VBUS_VBUS1") (pintype "bidirectional"))
      (node (ref "J5") (pin "VBUS2") (pinfunction "VBUS_VBUS2") (pintype "bidirectional"))
      (node (ref "L6") (pin "1") (pinfunction "1_1") (pintype "passive"))
    )
    (net (code "45") (name "Net-(JP3-PadSLEEVE)") (class "Default")
      (node (ref "JP3") (pin "SLEEVE") (pinfunction "SLEEVE_SLEEVE") (pintype "bidirectional"))
      (node (ref "R41") (pin "2") (pinfunction "2_2") (pintype "passive"))
    )
    (net (code "46") (name "Net-(LED1-0)") (class "Default")
      (node (ref "LED1") (pin "1") (pinfunction "0_1") (pintype "passive"))
      (node (ref "LED1") (pin "2") (pinfunction "1_2") (pintype "passive"))
      (node (ref "R49") (pin "2") (pinfunction "2_2") (pintype "passive"))
    )
    (net (code "47") (name "Net-(LED1-3)") (class "Default")
      (node (ref "LED1") (pin "4") (pinfunction "3_4") (pintype "passive"))
      (node (ref "R48") (pin "2") (pinfunction "2_2") (pintype "passive"))
    )
    (net (code "48") (name "Net-(LED1-5)") (class "Default")
      (node (ref "LED1") (pin "6") (pinfunction "5_6") (pintype "passive"))
      (node (ref "R51") (pin "1") (pinfunction "1_1") (pintype "passive"))
    )
    (net (code "49") (name "Net-(Q3-S)") (class "Default")
      (node (ref "C37") (pin "2") (pinfunction "2_2") (pintype "passive"))
      (node (ref "D10") (pin "C") (pinfunction "C_C") (pintype "passive"))
      (node (ref "Q3") (pin "2") (pinfunction "S_2") (pintype "passive"))
      (node (ref "R13") (pin "2") (pinfunction "2_2") (pintype "passive"))
      (node (ref "S2") (pin "3") (pinfunction "3_3") (pintype "bidirectional"))
      (node (ref "U3") (pin "1") (pinfunction "IN_1") (pintype "input"))
    )
    (net (code "50") (name "Net-(R1-Pad2)") (class "Default")
      (node (ref "R1") (pin "2") (pinfunction "2_2") (pintype "passive"))
      (node (ref "S2") (pin "1") (pinfunction "1_1") (pintype "bidirectional"))
    )
    (net (code "51") (name "Net-(U$3-BG)") (class "Default")
      (node (ref "C8") (pin "1") (pinfunction "1_1") (pintype "passive"))
      (node (ref "U$3") (pin "7") (pinfunction "BG_7") (pintype "bidirectional"))
    )
    (net (code "52") (name "Net-(U$3-XIN)") (class "Default")
      (node (ref "C6") (pin "2") (pinfunction "2_2") (pintype "passive"))
      (node (ref "U$3") (pin "38") (pinfunction "XIN_38") (pintype "bidirectional"))
      (node (ref "U$4") (pin "2") (pinfunction "2_2") (pintype "passive"))
    )
    (net (code "53") (name "Net-(U$3-XOUT)") (class "Default")
      (node (ref "C7") (pin "2") (pinfunction "2_2") (pintype "passive"))
      (node (ref "U$3") (pin "37") (pinfunction "XOUT_37") (pintype "bidirectional"))
      (node (ref "U$4") (pin "1") (pinfunction "1_1") (pintype "passive"))
    )
    (net (code "54") (name "Net-(U$19-1)") (class "Default")
      (node (ref "C1") (pin "1") (pinfunction "1_1") (pintype "passive"))
      (node (ref "U$19") (pin "P$1") (pinfunction "1_P$1") (pintype "passive"))
      (node (ref "U4") (pin "13") (pinfunction "IO1_13") (pintype "bidirectional"))
    )
    (net (code "55") (name "Net-(U$19-2)") (class "Default")
      (node (ref "C15") (pin "2") (pinfunction "2_2") (pintype "passive"))
      (node (ref "U$19") (pin "P$2") (pinfunction "2_P$2") (pintype "passive"))
      (node (ref "U4") (pin "12") (pinfunction "IO0_12") (pintype "bidirectional"))
    )
    (net (code "56") (name "Net-(U$30-BIN)") (class "Default")
      (node (ref "C67") (pin "1") (pinfunction "1_1") (pintype "passive"))
      (node (ref "C69") (pin "1") (pinfunction "1_1") (pintype "passive"))
      (node (ref "R42") (pin "2") (pinfunction "2_2") (pintype "passive"))
      (node (ref "U$30") (pin "A3") (pinfunction "BIN_A3") (pintype "bidirectional"))
    )
    (net (code "57") (name "Net-(U$30-BIP)") (class "Default")
      (node (ref "C68") (pin "1") (pinfunction "1_1") (pintype "passive"))
      (node (ref "C69") (pin "2") (pinfunction "2_2") (pintype "passive"))
      (node (ref "R43") (pin "2") (pinfunction "2_2") (pintype "passive"))
      (node (ref "U$30") (pin "A4") (pinfunction "BIP_A4") (pintype "bidirectional"))
    )
    (net (code "58") (name "Net-(U$30-CAPN)") (class "Default")
      (node (ref "C26") (pin "2") (pinfunction "2_2") (pintype "passive"))
      (node (ref "U$30") (pin "B5") (pinfunction "CAPN_B5") (pintype "bidirectional"))
    )
    (net (code "59") (name "Net-(U$30-CAPP)") (class "Default")
      (node (ref "C26") (pin "1") (pinfunction "1_1") (pintype "passive"))
      (node (ref "U$30") (pin "B6") (pinfunction "CAPP_B6") (pintype "bidirectional"))
    )
    (net (code "60") (name "Net-(U$30-CPLL)") (class "Default")
      (node (ref "C29") (pin "1") (pinfunction "1_1") (pintype "passive"))
      (node (ref "U$30") (pin "C6") (pinfunction "CPLL_C6") (pintype "bidirectional"))
    )
    (net (code "61") (name "Net-(U$30-DRVN)") (class "Default")
      (node (ref "C66") (pin "2") (pinfunction "2_2") (pintype "passive"))
      (node (ref "U$30") (pin "A2") (pinfunction "DRVN_A2") (pintype "bidirectional"))
    )
    (net (code "62") (name "Net-(U$30-DRVP)") (class "Default")
      (node (ref "C63") (pin "2") (pinfunction "2_2") (pintype "passive"))
      (node (ref "U$30") (pin "A1") (pinfunction "DRVP_A1") (pintype "bidirectional"))
    )
    (net (code "63") (name "Net-(U$30-RBIAS)") (class "Default")
      (node (ref "R44") (pin "1") (pinfunction "1_1") (pintype "passive"))
      (node (ref "U$30") (pin "B2") (pinfunction "RBIAS_B2") (pintype "bidirectional"))
    )
    (net (code "64") (name "Net-(U$30-VBG)") (class "Default")
      (node (ref "C34") (pin "1") (pinfunction "1_1") (pintype "passive"))
      (node (ref "U$30") (pin "B1") (pinfunction "VBG_B1") (pintype "bidirectional"))
    )
    (net (code "65") (name "Net-(U$30-VREF)") (class "Default")
      (node (ref "C32") (pin "1") (pinfunction "1_1") (pintype "passive"))
      (node (ref "U$30") (pin "D1") (pinfunction "VREF_D1") (pintype "bidirectional"))
    )
    (net (code "66") (name "Net-(U4-IO2)") (class "Default")
      (node (ref "R2") (pin "2") (pinfunction "2_2") (pintype "passive"))
      (node (ref "U4") (pin "5") (pinfunction "IO2_5") (pintype "bidirectional"))
    )
    (net (code "67") (name "Net-(U4-IO8)") (class "Default")
      (node (ref "SWIO2") (pin "TP") (pinfunction "TP_TP") (pintype "input"))
      (node (ref "U4") (pin "22") (pinfunction "IO8_22") (pintype "bidirectional"))
    )
    (net (code "68") (name "Net-(U4-RXD0)") (class "Default")
      (node (ref "SWIO8") (pin "TP") (pinfunction "TP_TP") (pintype "input"))
      (node (ref "U4") (pin "30") (pinfunction "RXD0_30") (pintype "bidirectional"))
    )
    (net (code "69") (name "Net-(U4-TXD0)") (class "Default")
      (node (ref "SWIO9") (pin "TP") (pinfunction "TP_TP") (pintype "input"))
      (node (ref "U4") (pin "31") (pinfunction "TXD0_31") (pintype "bidirectional"))
    )
    (net (code "70") (name "Net-(U5-PROG)") (class "Default")
      (node (ref "R11") (pin "2") (pinfunction "2_2") (pintype "passive"))
      (node (ref "U5") (pin "5") (pinfunction "PROG_5") (pintype "input"))
    )
    (net (code "71") (name "Net-(U7-GPIO0)") (class "Default")
      (node (ref "R3") (pin "1") (pinfunction "1_1") (pintype "passive"))
      (node (ref "U7") (pin "2") (pinfunction "GPIO0_2") (pintype "bidirectional"))
    )
    (net (code "72") (name "Net-(U7-GPIO1)") (class "Default")
      (node (ref "R6") (pin "1") (pinfunction "1_1") (pintype "passive"))
      (node (ref "U7") (pin "3") (pinfunction "GPIO1_3") (pintype "bidirectional"))
    )
    (net (code "73") (name "Net-(U7-GPIO2)") (class "Default")
      (node (ref "R4") (pin "1") (pinfunction "1_1") (pintype "passive"))
      (node (ref "U7") (pin "4") (pinfunction "GPIO2_4") (pintype "bidirectional"))
    )
    (net (code "74") (name "Net-(U7-GPIO3)") (class "Default")
      (node (ref "R14") (pin "1") (pinfunction "1_1") (pintype "passive"))
      (node (ref "U7") (pin "5") (pinfunction "GPIO3_5") (pintype "bidirectional"))
    )
    (net (code "75") (name "Net-(U7-GPIO4)") (class "Default")
      (node (ref "R17") (pin "1") (pinfunction "1_1") (pintype "passive"))
      (node (ref "U7") (pin "6") (pinfunction "GPIO4_6") (pintype "bidirectional"))
    )
    (net (code "76") (name "Net-(U7-GPIO8)") (class "Default")
      (node (ref "R28") (pin "1") (pinfunction "1_1") (pintype "passive"))
      (node (ref "U7") (pin "11") (pinfunction "GPIO8_11") (pintype "bidirectional"))
    )
    (net (code "77") (name "Net-(U7-GPIO10)") (class "Default")
      (node (ref "R29") (pin "1") (pinfunction "1_1") (pintype "passive"))
      (node (ref "U7") (pin "13") (pinfunction "GPIO10_13") (pintype "bidirectional"))
    )
    (net (code "78") (name "Net-(U7-GPIO11)") (class "Default")
      (node (ref "R31") (pin "1") (pinfunction "1_1") (pintype "passive"))
      (node (ref "U7") (pin "14") (pinfunction "GPIO11_14") (pintype "bidirectional"))
    )
    (net (code "79") (name "Net-(U7-GPIO24)") (class "Default")
      (node (ref "R37") (pin "1") (pinfunction "1_1") (pintype "passive"))
      (node (ref "U7") (pin "36") (pinfunction "GPIO24_36") (pintype "bidirectional"))
    )
    (net (code "80") (name "Net-(U7-GPIO25)") (class "Default")
      (node (ref "R36") (pin "1") (pinfunction "1_1") (pintype "passive"))
      (node (ref "U7") (pin "37") (pinfunction "GPIO25_37") (pintype "bidirectional"))
    )
    (net (code "81") (name "Net-(U7-SWCLK)") (class "Default")
      (node (ref "R9") (pin "2") (pinfunction "2_2") (pintype "passive"))
      (node (ref "U7") (pin "24") (pinfunction "SWCLK_24") (pintype "bidirectional"))
    )
    (net (code "82") (name "Net-(U7-SWDIO)") (class "Default")
      (node (ref "R12") (pin "2") (pinfunction "2_2") (pintype "passive"))
      (node (ref "U7") (pin "25") (pinfunction "SWDIO_25") (pintype "bidirectional"))
    )
    (net (code "83") (name "Net-(U7-USB_D+)") (class "Default")
      (node (ref "R20") (pin "2") (pinfunction "2_2") (pintype "passive"))
      (node (ref "U7") (pin "47") (pinfunction "USB_D+_47") (pintype "bidirectional"))
    )
    (net (code "84") (name "Net-(U7-USB_D-)") (class "Default")
      (node (ref "R19") (pin "2") (pinfunction "2_2") (pintype "passive"))
      (node (ref "U7") (pin "46") (pinfunction "USB_D-_46") (pintype "bidirectional"))
    )
    (net (code "85") (name "Net-(U7-XIN)") (class "Default")
      (node (ref "C36") (pin "2") (pinfunction "2_2") (pintype "passive"))
      (node (ref "U7") (pin "20") (pinfunction "XIN_20") (pintype "bidirectional"))
      (node (ref "Y2") (pin "P3") (pinfunction "2_P3") (pintype "passive"))
    )
    (net (code "86") (name "Net-(U7-XOUT)") (class "Default")
      (node (ref "R18") (pin "2") (pinfunction "2_2") (pintype "passive"))
      (node (ref "U7") (pin "21") (pinfunction "XOUT_21") (pintype "bidirectional"))
    )
    (net (code "87") (name "Net-(Y2-1)") (class "Default")
      (node (ref "C31") (pin "2") (pinfunction "2_2") (pintype "passive"))
      (node (ref "R18") (pin "1") (pinfunction "1_1") (pintype "passive"))
      (node (ref "Y2") (pin "P1") (pinfunction "1_P1") (pintype "passive"))
    )
    (net (code "88") (name "QSPI-0") (class "Default")
      (node (ref "U6") (pin "5") (pinfunction "D0/DI_5") (pintype "bidirectional"))
      (node (ref "U7") (pin "53") (pinfunction "QSPI_SD0_53") (pintype "bidirectional"))
    )
    (net (code "89") (name "QSPI-1") (class "Default")
      (node (ref "U6") (pin "2") (pinfunction "D1/DO_2") (pintype "bidirectional"))
      (node (ref "U7") (pin "55") (pinfunction "QSPI_SD1_55") (pintype "bidirectional"))
    )
    (net (code "90") (name "QSPI-2") (class "Default")
      (node (ref "U6") (pin "3") (pinfunction "D2/~{WP}_3") (pintype "bidirectional"))
      (node (ref "U7") (pin "54") (pinfunction "QSPI_SD2_54") (pintype "bidirectional"))
    )
    (net (code "91") (name "QSPI-3") (class "Default")
      (node (ref "U6") (pin "7") (pinfunction "D3/~{HOLD}_7") (pintype "bidirectional"))
      (node (ref "U7") (pin "51") (pinfunction "QSPI_SD3_51") (pintype "bidirectional"))
    )
    (net (code "92") (name "QSPI-CLK") (class "Default")
      (node (ref "U6") (pin "6") (pinfunction "CLK_6") (pintype "bidirectional"))
      (node (ref "U7") (pin "52") (pinfunction "QSPI_SCLK_52") (pintype "bidirectional"))
    )
    (net (code "93") (name "QSPI-CS") (class "Default")
      (node (ref "R21") (pin "1") (pinfunction "1_1") (pintype "passive"))
      (node (ref "R22") (pin "1") (pinfunction "1_1") (pintype "passive"))
      (node (ref "U6") (pin "1") (pinfunction "~{CS}_1") (pintype "bidirectional"))
      (node (ref "U7") (pin "56") (pinfunction "QSPI_~{CS}_56") (pintype "bidirectional"))
    )
    (net (code "94") (name "RX_ANA_SUP") (class "Default")
      (node (ref "C11") (pin "1") (pinfunction "1_1") (pintype "passive"))
      (node (ref "C18") (pin "1") (pinfunction "1_1") (pintype "passive"))
      (node (ref "D2") (pin "3") (pinfunction "A_3") (pintype "passive"))
      (node (ref "D3") (pin "3") (pinfunction "A_3") (pintype "passive"))
      (node (ref "L2") (pin "2") (pinfunction "2_2") (pintype "passive"))
      (node (ref "U$3") (pin "33") (pinfunction "RX_ANA_SUP_33") (pintype "bidirectional"))
      (node (ref "U$3") (pin "39") (pinfunction "RX_ANA_SUP_39") (pintype "bidirectional"))
    )
    (net (code "95") (name "RX_DIG_SUP") (class "Default")
      (node (ref "C12") (pin "1") (pinfunction "1_1") (pintype "passive"))
      (node (ref "C19") (pin "1") (pinfunction "1_1") (pintype "passive"))
      (node (ref "L1") (pin "2") (pinfunction "2_2") (pintype "passive"))
      (node (ref "R47") (pin "1") (pinfunction "1_1") (pintype "passive"))
      (node (ref "U$3") (pin "31") (pinfunction "RX_DIG_SUP_31") (pintype "bidirectional"))
    )
    (net (code "96") (name "SCK") (class "Default")
      (node (ref "R4") (pin "2") (pinfunction "2_2") (pintype "passive"))
      (node (ref "U$3") (pin "24") (pinfunction "SCLK_24") (pintype "bidirectional"))
      (node (ref "U$30") (pin "E5") (pinfunction "SCLK_E5") (pintype "bidirectional"))
    )
    (net (code "97") (name "SD_CS") (class "Default")
      (node (ref "J4") (pin "2") (pinfunction "DATA3/CD_2") (pintype "bidirectional"))
      (node (ref "R5") (pin "1") (pinfunction "1_1") (pintype "passive"))
      (node (ref "U7") (pin "16") (pinfunction "GPIO13_16") (pintype "bidirectional"))
    )
    (net (code "98") (name "SPO2_CS") (class "Default")
      (node (ref "U$3") (pin "27") (pinfunction "SPISTE_27") (pintype "bidirectional"))
      (node (ref "U7") (pin "30") (pinfunction "GPIO19_30") (pintype "bidirectional"))
    )
    (net (code "99") (name "SPO2_DRDY") (class "Default")
      (node (ref "U$3") (pin "28") (pinfunction "ADC_RDY_28") (pintype "bidirectional"))
      (node (ref "U7") (pin "28") (pinfunction "GPIO17_28") (pintype "bidirectional"))
    )
    (net (code "100") (name "SPO2_START") (class "Default")
      (node (ref "U$3") (pin "20") (pinfunction "AFE_~{PDN}_20") (pintype "bidirectional"))
      (node (ref "U7") (pin "29") (pinfunction "GPIO18_29") (pintype "bidirectional"))
    )
    (net (code "101") (name "SW1") (class "Default")
      (node (ref "K1") (pin "26") (pinfunction "26_26") (pintype "passive"))
      (node (ref "U7") (pin "15") (pinfunction "GPIO12_15") (pintype "bidirectional"))
    )
    (net (code "102") (name "SW2") (class "Default")
      (node (ref "K1") (pin "31") (pinfunction "31_31") (pintype "passive"))
      (node (ref "U7") (pin "17") (pinfunction "GPIO14_17") (pintype "bidirectional"))
    )
    (net (code "103") (name "SW3") (class "Default")
      (node (ref "K1") (pin "16") (pinfunction "16_16") (pintype "passive"))
      (node (ref "U7") (pin "18") (pinfunction "GPIO15_18") (pintype "bidirectional"))
    )
    (net (code "104") (name "SWDCK") (class "Default")
      (node (ref "J6") (pin "1") (pinfunction "1_1") (pintype "passive"))
      (node (ref "R9") (pin "1") (pinfunction "1_1") (pintype "passive"))
    )
    (net (code "105") (name "SWDIO") (class "Default")
      (node (ref "J6") (pin "3") (pinfunction "3_3") (pintype "passive"))
      (node (ref "R12") (pin "1") (pinfunction "1_1") (pintype "passive"))
    )
    (net (code "106") (name "TFT_BKL") (class "Default")
      (node (ref "K1") (pin "12") (pinfunction "12_12") (pintype "passive"))
      (node (ref "U7") (pin "27") (pinfunction "GPIO16_27") (pintype "bidirectional"))
    )
    (net (code "107") (name "TFT_CS") (class "Default")
      (node (ref "K1") (pin "24") (pinfunction "24_24") (pintype "passive"))
      (node (ref "U7") (pin "41") (pinfunction "GPIO29/ADC3_41") (pintype "bidirectional"))
    )
    (net (code "108") (name "TFT_DC") (class "Default")
      (node (ref "K1") (pin "22") (pinfunction "22_22") (pintype "passive"))
      (node (ref "U7") (pin "35") (pinfunction "GPIO23_35") (pintype "bidirectional"))
    )
    (net (code "109") (name "TFT_RESET") (class "Default")
      (node (ref "K1") (pin "36") (pinfunction "36_36") (pintype "passive"))
      (node (ref "U7") (pin "40") (pinfunction "GPIO28/ADC2_40") (pintype "bidirectional"))
    )
    (net (code "110") (name "TMP_SCL") (class "Default")
      (node (ref "D13") (pin "2") (pinfunction "2_2") (pintype "bidirectional"))
      (node (ref "D16") (pin "1") (pinfunction "1_1") (pintype "bidirectional"))
      (node (ref "J1") (pin "4") (pinfunction "4_4") (pintype "passive"))
      (node (ref "K1") (pin "5") (pinfunction "5_5") (pintype "passive"))
      (node (ref "R7") (pin "2") (pinfunction "2_2") (pintype "passive"))
      (node (ref "U$38") (pin "6") (pinfunction "SCL_6") (pintype "bidirectional"))
      (node (ref "U1") (pin "7") (pinfunction "SCL_7") (pintype "input"))
      (node (ref "U7") (pin "9") (pinfunction "GPIO7_9") (pintype "bidirectional"))
    )
    (net (code "111") (name "TMP_SDA") (class "Default")
      (node (ref "D14") (pin "2") (pinfunction "2_2") (pintype "bidirectional"))
      (node (ref "D15") (pin "1") (pinfunction "1_1") (pintype "bidirectional"))
      (node (ref "J1") (pin "3") (pinfunction "3_3") (pintype "passive"))
      (node (ref "K1") (pin "3") (pinfunction "3_3") (pintype "passive"))
      (node (ref "R33") (pin "2") (pinfunction "2_2") (pintype "passive"))
      (node (ref "U$38") (pin "5") (pinfunction "SDA_5") (pintype "bidirectional"))
      (node (ref "U1") (pin "8") (pinfunction "SDA_8") (pintype "bidirectional"))
      (node (ref "U7") (pin "8") (pinfunction "GPIO6_8") (pintype "bidirectional"))
    )
    (net (code "112") (name "TX_CTRL_SUP") (class "Default")
      (node (ref "C27") (pin "1") (pinfunction "1_1") (pintype "passive"))
      (node (ref "C9") (pin "1") (pinfunction "1_1") (pintype "passive"))
      (node (ref "L4") (pin "2") (pinfunction "2_2") (pintype "passive"))
      (node (ref "U$3") (pin "11") (pinfunction "TX_CTRL_SUP_11") (pintype "bidirectional"))
    )
    (net (code "113") (name "TX_N") (class "Default")
      (node (ref "D1") (pin "1") (pinfunction "CA_1") (pintype "passive"))
      (node (ref "U$3") (pin "14") (pinfunction "TXN_14") (pintype "bidirectional"))
      (node (ref "X1") (pin "3") (pinfunction "3_3") (pintype "passive"))
    )
    (net (code "114") (name "TX_P") (class "Default")
      (node (ref "D5") (pin "1") (pinfunction "CA_1") (pintype "passive"))
      (node (ref "U$3") (pin "15") (pinfunction "TXP_15") (pintype "bidirectional"))
      (node (ref "X1") (pin "2") (pinfunction "2_2") (pintype "passive"))
    )
    (net (code "115") (name "U0RXD") (class "Default")
      (node (ref "J7") (pin "1") (pinfunction "1_1") (pintype "passive"))
      (node (ref "K1") (pin "8") (pinfunction "8_8") (pintype "passive"))
      (node (ref "R6") (pin "2") (pinfunction "2_2") (pintype "passive"))
    )
    (net (code "116") (name "U0TXD") (class "Default")
      (node (ref "J7") (pin "3") (pinfunction "3_3") (pintype "passive"))
      (node (ref "K1") (pin "10") (pinfunction "10_10") (pintype "passive"))
      (node (ref "R3") (pin "2") (pinfunction "2_2") (pintype "passive"))
    )
    (net (code "117") (name "USB_D+") (class "Default")
      (node (ref "R8") (pin "2") (pinfunction "2_2") (pintype "passive"))
      (node (ref "U4") (pin "27") (pinfunction "IO19_27") (pintype "bidirectional"))
    )
    (net (code "118") (name "USB_D-") (class "Default")
      (node (ref "R10") (pin "2") (pinfunction "2_2") (pintype "passive"))
      (node (ref "U4") (pin "26") (pinfunction "IO18_26") (pintype "bidirectional"))
    )
    (net (code "119") (name "USB_F_RP_D+") (class "Default")
      (node (ref "D4") (pin "2") (pinfunction "2_2") (pintype "bidirectional"))
      (node (ref "J3") (pin "A6") (pinfunction "D+_A6") (pintype "bidirectional"))
      (node (ref "J3") (pin "B6") (pinfunction "D+_B6") (pintype "bidirectional"))
      (node (ref "R20") (pin "1") (pinfunction "1_1") (pintype "passive"))
    )
    (net (code "120") (name "USB_F_RP_D-") (class "Default")
      (node (ref "D7") (pin "2") (pinfunction "2_2") (pintype "bidirectional"))
      (node (ref "J3") (pin "A7") (pinfunction "D-_A7") (pintype "bidirectional"))
      (node (ref "J3") (pin "B7") (pinfunction "D-_B7") (pintype "bidirectional"))
      (node (ref "R19") (pin "1") (pinfunction "1_1") (pintype "passive"))
    )
    (net (code "121") (name "VBAT") (class "Default")
      (node (ref "C5") (pin "1") (pinfunction "1_1") (pintype "passive"))
      (node (ref "C65") (pin "1") (pinfunction "1_1") (pintype "passive"))
      (node (ref "JP6") (pin "2") (pinfunction "2_2") (pintype "passive"))
      (node (ref "Q3") (pin "3") (pinfunction "D_3") (pintype "passive"))
      (node (ref "U1") (pin "2") (pinfunction "CELL_2") (pintype "power_in"))
      (node (ref "U1") (pin "3") (pinfunction "VDD_3") (pintype "power_in"))
      (node (ref "U5") (pin "3") (pinfunction "VBAT_3") (pintype "power_in"))
    )
    (net (code "122") (name "VBUS") (class "Default")
      (node (ref "C21") (pin "2") (pinfunction "2_2") (pintype "passive"))
      (node (ref "C23") (pin "2") (pinfunction "2_2") (pintype "passive"))
      (node (ref "D6") (pin "C") (pinfunction "C_C") (pintype "passive"))
      (node (ref "D9") (pin "A") (pinfunction "A_A") (pintype "passive"))
      (node (ref "L5") (pin "2") (pinfunction "2_2") (pintype "passive"))
      (node (ref "L6") (pin "2") (pinfunction "2_2") (pintype "passive"))
      (node (ref "TP5") (pin "TP") (pinfunction "TP_TP") (pintype "input"))
    )
    (net (code "123") (name "VCM") (class "Default")
      (node (ref "C13") (pin "1") (pinfunction "1_1") (pintype "passive"))
      (node (ref "U$3") (pin "4") (pinfunction "VCM_4") (pintype "bidirectional"))
    )
    (net (code "124") (name "VDD") (class "Default")
      (node (ref "C64") (pin "1") (pinfunction "1_1") (pintype "passive"))
      (node (ref "D10") (pin "A") (pinfunction "A_A") (pintype "passive"))
      (node (ref "D8") (pin "C") (pinfunction "C_C") (pintype "passive"))
      (node (ref "D9") (pin "C") (pinfunction "C_C") (pintype "passive"))
      (node (ref "LED1") (pin "5") (pinfunction "4_5") (pintype "passive"))
      (node (ref "Q3") (pin "1") (pinfunction "G_1") (pintype "passive"))
      (node (ref "R30") (pin "2") (pinfunction "2_2") (pintype "passive"))
      (node (ref "SWIO7") (pin "TP") (pinfunction "TP_TP") (pintype "input"))
      (node (ref "U5") (pin "4") (pinfunction "VIN_4") (pintype "power_in"))
    )
    (net (code "125") (name "unconnected-(J4-DATA1-Pad8)") (class "Default")
      (node (ref "J4") (pin "8") (pinfunction "DATA1_8") (pintype "bidirectional"))
    )
    (net (code "126") (name "unconnected-(J4-DATA2-Pad1)") (class "Default")
      (node (ref "J4") (pin "1") (pinfunction "DATA2_1") (pintype "bidirectional"))
    )
    (net (code "127") (name "unconnected-(J4-DETECH-Pad9)") (class "Default")
      (node (ref "J4") (pin "9") (pinfunction "DETECH_9") (pintype "passive"))
    )
    (net (code "128") (name "unconnected-(K1-Pad7)") (class "Default")
      (node (ref "K1") (pin "7") (pinfunction "7_7") (pintype "passive"))
    )
    (net (code "129") (name "unconnected-(K1-Pad11)") (class "Default")
      (node (ref "K1") (pin "11") (pinfunction "11_11") (pintype "passive"))
    )
    (net (code "130") (name "unconnected-(K1-Pad13)") (class "Default")
      (node (ref "K1") (pin "13") (pinfunction "13_13") (pintype "passive"))
    )
    (net (code "131") (name "unconnected-(K1-Pad15)") (class "Default")
      (node (ref "K1") (pin "15") (pinfunction "15_15") (pintype "passive"))
    )
    (net (code "132") (name "unconnected-(K1-Pad18)") (class "Default")
      (node (ref "K1") (pin "18") (pinfunction "18_18") (pintype "passive"))
    )
    (net (code "133") (name "unconnected-(K1-Pad27)") (class "Default")
      (node (ref "K1") (pin "27") (pinfunction "27_27") (pintype "passive"))
    )
    (net (code "134") (name "unconnected-(K1-Pad28)") (class "Default")
      (node (ref "K1") (pin "28") (pinfunction "28_28") (pintype "passive"))
    )
    (net (code "135") (name "unconnected-(K1-Pad32)") (class "Default")
      (node (ref "K1") (pin "32") (pinfunction "32_32") (pintype "passive"))
    )
    (net (code "136") (name "unconnected-(K1-Pad33)") (class "Default")
      (node (ref "K1") (pin "33") (pinfunction "33_33") (pintype "passive"))
    )
    (net (code "137") (name "unconnected-(K1-Pad35)") (class "Default")
      (node (ref "K1") (pin "35") (pinfunction "35_35") (pintype "passive"))
    )
    (net (code "138") (name "unconnected-(K1-Pad37)") (class "Default")
      (node (ref "K1") (pin "37") (pinfunction "37_37") (pintype "passive"))
    )
    (net (code "139") (name "unconnected-(K1-Pad38)") (class "Default")
      (node (ref "K1") (pin "38") (pinfunction "38_38") (pintype "passive"))
    )
    (net (code "140") (name "unconnected-(K1-Pad40)") (class "Default")
      (node (ref "K1") (pin "40") (pinfunction "40_40") (pintype "passive"))
    )
    (net (code "141") (name "unconnected-(S2-5-Pad4)") (class "Default")
      (node (ref "S2") (pin "4") (pinfunction "5_4") (pintype "bidirectional"))
    )
    (net (code "142") (name "unconnected-(S2-6_-_C-Pad5)") (class "Default")
      (node (ref "S2") (pin "5") (pinfunction "6_-_C_5") (pintype "bidirectional"))
    )
    (net (code "143") (name "unconnected-(S2-7-Pad6)") (class "Default")
      (node (ref "S2") (pin "6") (pinfunction "7_6") (pintype "bidirectional"))
    )
    (net (code "144") (name "unconnected-(SW1-P-PadA)") (class "Default")
      (node (ref "SW1") (pin "A") (pinfunction "P_A") (pintype "passive"))
    )
    (net (code "145") (name "unconnected-(SW1-S-PadB)") (class "Default")
      (node (ref "SW1") (pin "B") (pinfunction "S_B") (pintype "passive"))
    )
    (net (code "146") (name "unconnected-(SW2-P-PadA)") (class "Default")
      (node (ref "SW2") (pin "A") (pinfunction "P_A") (pintype "passive"))
    )
    (net (code "147") (name "unconnected-(SW2-S-PadB)") (class "Default")
      (node (ref "SW2") (pin "B") (pinfunction "S_B") (pintype "passive"))
    )
    (net (code "148") (name "unconnected-(SW4-P-PadA)") (class "Default")
      (node (ref "SW4") (pin "A") (pinfunction "P_A") (pintype "passive"))
    )
    (net (code "149") (name "unconnected-(SW4-S-PadB)") (class "Default")
      (node (ref "SW4") (pin "B") (pinfunction "S_B") (pintype "passive"))
    )
    (net (code "150") (name "unconnected-(SW5-P-PadA)") (class "Default")
      (node (ref "SW5") (pin "A") (pinfunction "P_A") (pintype "passive"))
    )
    (net (code "151") (name "unconnected-(SW5-S-PadB)") (class "Default")
      (node (ref "SW5") (pin "B") (pinfunction "S_B") (pintype "passive"))
    )
    (net (code "152") (name "unconnected-(U$3-CLKOUT-Pad30)") (class "Default")
      (node (ref "U$3") (pin "30") (pinfunction "CLKOUT_30") (pintype "bidirectional"))
    )
    (net (code "153") (name "unconnected-(U$3-DIAG_END-Pad21)") (class "Default")
      (node (ref "U$3") (pin "21") (pinfunction "DIAG_END_21") (pintype "bidirectional"))
    )
    (net (code "154") (name "unconnected-(U$3-DNC-Pad5)") (class "Default")
      (node (ref "U$3") (pin "5") (pinfunction "DNC_5") (pintype "bidirectional"))
    )
    (net (code "155") (name "unconnected-(U$3-DNC-Pad6)") (class "Default")
      (node (ref "U$3") (pin "6") (pinfunction "DNC_6") (pintype "bidirectional"))
    )
    (net (code "156") (name "unconnected-(U$3-DNC-Pad10)") (class "Default")
      (node (ref "U$3") (pin "10") (pinfunction "DNC_10") (pintype "bidirectional"))
    )
    (net (code "157") (name "unconnected-(U$3-DNC-Pad34)") (class "Default")
      (node (ref "U$3") (pin "34") (pinfunction "DNC_34") (pintype "bidirectional"))
    )
    (net (code "158") (name "unconnected-(U$3-DNC-Pad35)") (class "Default")
      (node (ref "U$3") (pin "35") (pinfunction "DNC_35") (pintype "bidirectional"))
    )
    (net (code "159") (name "unconnected-(U$3-LED_ALM-Pad22)") (class "Default")
      (node (ref "U$3") (pin "22") (pinfunction "LED_ALM_22") (pintype "bidirectional"))
    )
    (net (code "160") (name "unconnected-(U$3-PD_ALM-Pad23)") (class "Default")
      (node (ref "U$3") (pin "23") (pinfunction "PD_ALM_23") (pintype "bidirectional"))
    )
    (net (code "161") (name "unconnected-(U$3-RSVD-Pad9)") (class "Default")
      (node (ref "U$3") (pin "9") (pinfunction "RSVD_9") (pintype "bidirectional"))
    )
    (net (code "162") (name "unconnected-(U$24-0-Pad1)") (class "Default")
      (node (ref "U$24") (pin "1") (pinfunction "0_1") (pintype "passive"))
    )
    (net (code "163") (name "unconnected-(U$24-1-Pad4)") (class "Default")
      (node (ref "U$24") (pin "4") (pinfunction "1_4") (pintype "passive"))
    )
    (net (code "164") (name "unconnected-(U$26-NC-Pad4)") (class "Default")
      (node (ref "U$26") (pin "4") (pinfunction "NC_4") (pintype "bidirectional"))
    )
    (net (code "165") (name "unconnected-(U$30-AOUT-PadC2)") (class "Default")
      (node (ref "U$30") (pin "C2") (pinfunction "AOUT_C2") (pintype "bidirectional"))
    )
    (net (code "166") (name "unconnected-(U$31-NC-Pad1)") (class "Default")
      (node (ref "U$31") (pin "1") (pinfunction "NC_1") (pintype "bidirectional"))
    )
    (net (code "167") (name "unconnected-(U$38-NC-Pad1)") (class "Default")
      (node (ref "U$38") (pin "1") (pinfunction "NC_1") (pintype "bidirectional"))
    )
    (net (code "168") (name "unconnected-(U$38-NC-Pad2)") (class "Default")
      (node (ref "U$38") (pin "2") (pinfunction "NC_2") (pintype "bidirectional"))
    )
    (net (code "169") (name "unconnected-(U$38-NC-Pad3)") (class "Default")
      (node (ref "U$38") (pin "3") (pinfunction "NC_3") (pintype "bidirectional"))
    )
    (net (code "170") (name "unconnected-(U$38-NC-Pad7)") (class "Default")
      (node (ref "U$38") (pin "7") (pinfunction "NC_7") (pintype "bidirectional"))
    )
    (net (code "171") (name "unconnected-(U3-BP-Pad4)") (class "Default")
      (node (ref "U3") (pin "4") (pinfunction "BP_4") (pintype "input"))
    )
    (net (code "172") (name "unconnected-(U4-IO3-Pad6)") (class "Default")
      (node (ref "U4") (pin "6") (pinfunction "IO3_6") (pintype "bidirectional"))
    )
    (net (code "173") (name "unconnected-(U4-NC-Pad4)") (class "Default")
      (node (ref "U4") (pin "4") (pinfunction "NC_4") (pintype "no_connect"))
    )
    (net (code "174") (name "unconnected-(U4-NC-Pad7)") (class "Default")
      (node (ref "U4") (pin "7") (pinfunction "NC_7") (pintype "no_connect"))
    )
    (net (code "175") (name "unconnected-(U4-NC-Pad9)") (class "Default")
      (node (ref "U4") (pin "9") (pinfunction "NC_9") (pintype "no_connect"))
    )
    (net (code "176") (name "unconnected-(U4-NC-Pad10)") (class "Default")
      (node (ref "U4") (pin "10") (pinfunction "NC_10") (pintype "no_connect"))
    )
    (net (code "177") (name "unconnected-(U4-NC-Pad15)") (class "Default")
      (node (ref "U4") (pin "15") (pinfunction "NC_15") (pintype "no_connect"))
    )
    (net (code "178") (name "unconnected-(U4-NC-Pad17)") (class "Default")
      (node (ref "U4") (pin "17") (pinfunction "NC_17") (pintype "no_connect"))
    )
    (net (code "179") (name "unconnected-(U4-NC-Pad24)") (class "Default")
      (node (ref "U4") (pin "24") (pinfunction "NC_24") (pintype "no_connect"))
    )
    (net (code "180") (name "unconnected-(U4-NC-Pad25)") (class "Default")
      (node (ref "U4") (pin "25") (pinfunction "NC_25") (pintype "no_connect"))
    )
    (net (code "181") (name "unconnected-(U4-NC-Pad28)") (class "Default")
      (node (ref "U4") (pin "28") (pinfunction "NC_28") (pintype "no_connect"))
    )
    (net (code "182") (name "unconnected-(U4-NC-Pad29)") (class "Default")
      (node (ref "U4") (pin "29") (pinfunction "NC_29") (pintype "no_connect"))
    )
    (net (code "183") (name "unconnected-(U4-NC-Pad32)") (class "Default")
      (node (ref "U4") (pin "32") (pinfunction "NC_32") (pintype "no_connect"))
    )
    (net (code "184") (name "unconnected-(U4-NC-Pad33)") (class "Default")
      (node (ref "U4") (pin "33") (pinfunction "NC_33") (pintype "no_connect"))
    )
    (net (code "185") (name "unconnected-(U4-NC-Pad34)") (class "Default")
      (node (ref "U4") (pin "34") (pinfunction "NC_34") (pintype "no_connect"))
    )
    (net (code "186") (name "unconnected-(U4-NC-Pad35)") (class "Default")
      (node (ref "U4") (pin "35") (pinfunction "NC_35") (pintype "no_connect"))
    )
    (net (code "187") (name "unconnected-(X1-Pad1)") (class "Default")
      (node (ref "X1") (pin "1") (pinfunction "1_1") (pintype "passive"))
    )
    (net (code "188") (name "unconnected-(X1-Pad4)") (class "Default")
      (node (ref "X1") (pin "4") (pinfunction "4_4") (pintype "passive"))
    )
    (net (code "189") (name "unconnected-(X1-Pad6)") (class "Default")
      (node (ref "X1") (pin "6") (pinfunction "6_6") (pintype "passive"))
    )
    (net (code "190") (name "unconnected-(X1-Pad8)") (class "Default")
      (node (ref "X1") (pin "8") (pinfunction "8_8") (pintype "passive"))
    )
    (net (code "191") (name "~{ADC_RESET}") (class "Default")
      (node (ref "R47") (pin "2") (pinfunction "2_2") (pintype "passive"))
      (node (ref "U$3") (pin "29") (pinfunction "~{RESET}_29") (pintype "bidirectional"))
    )
    (net (code "192") (name "~{RESET}") (class "Default")
      (node (ref "SW5") (pin "B'") (pinfunction "S1_B'") (pintype "passive"))
      (node (ref "U7") (pin "26") (pinfunction "RUN_26") (pintype "bidirectional"))
    )
  )
)
